# main_controller.net
KiCad netlist of a schematic drawn in EAGLE
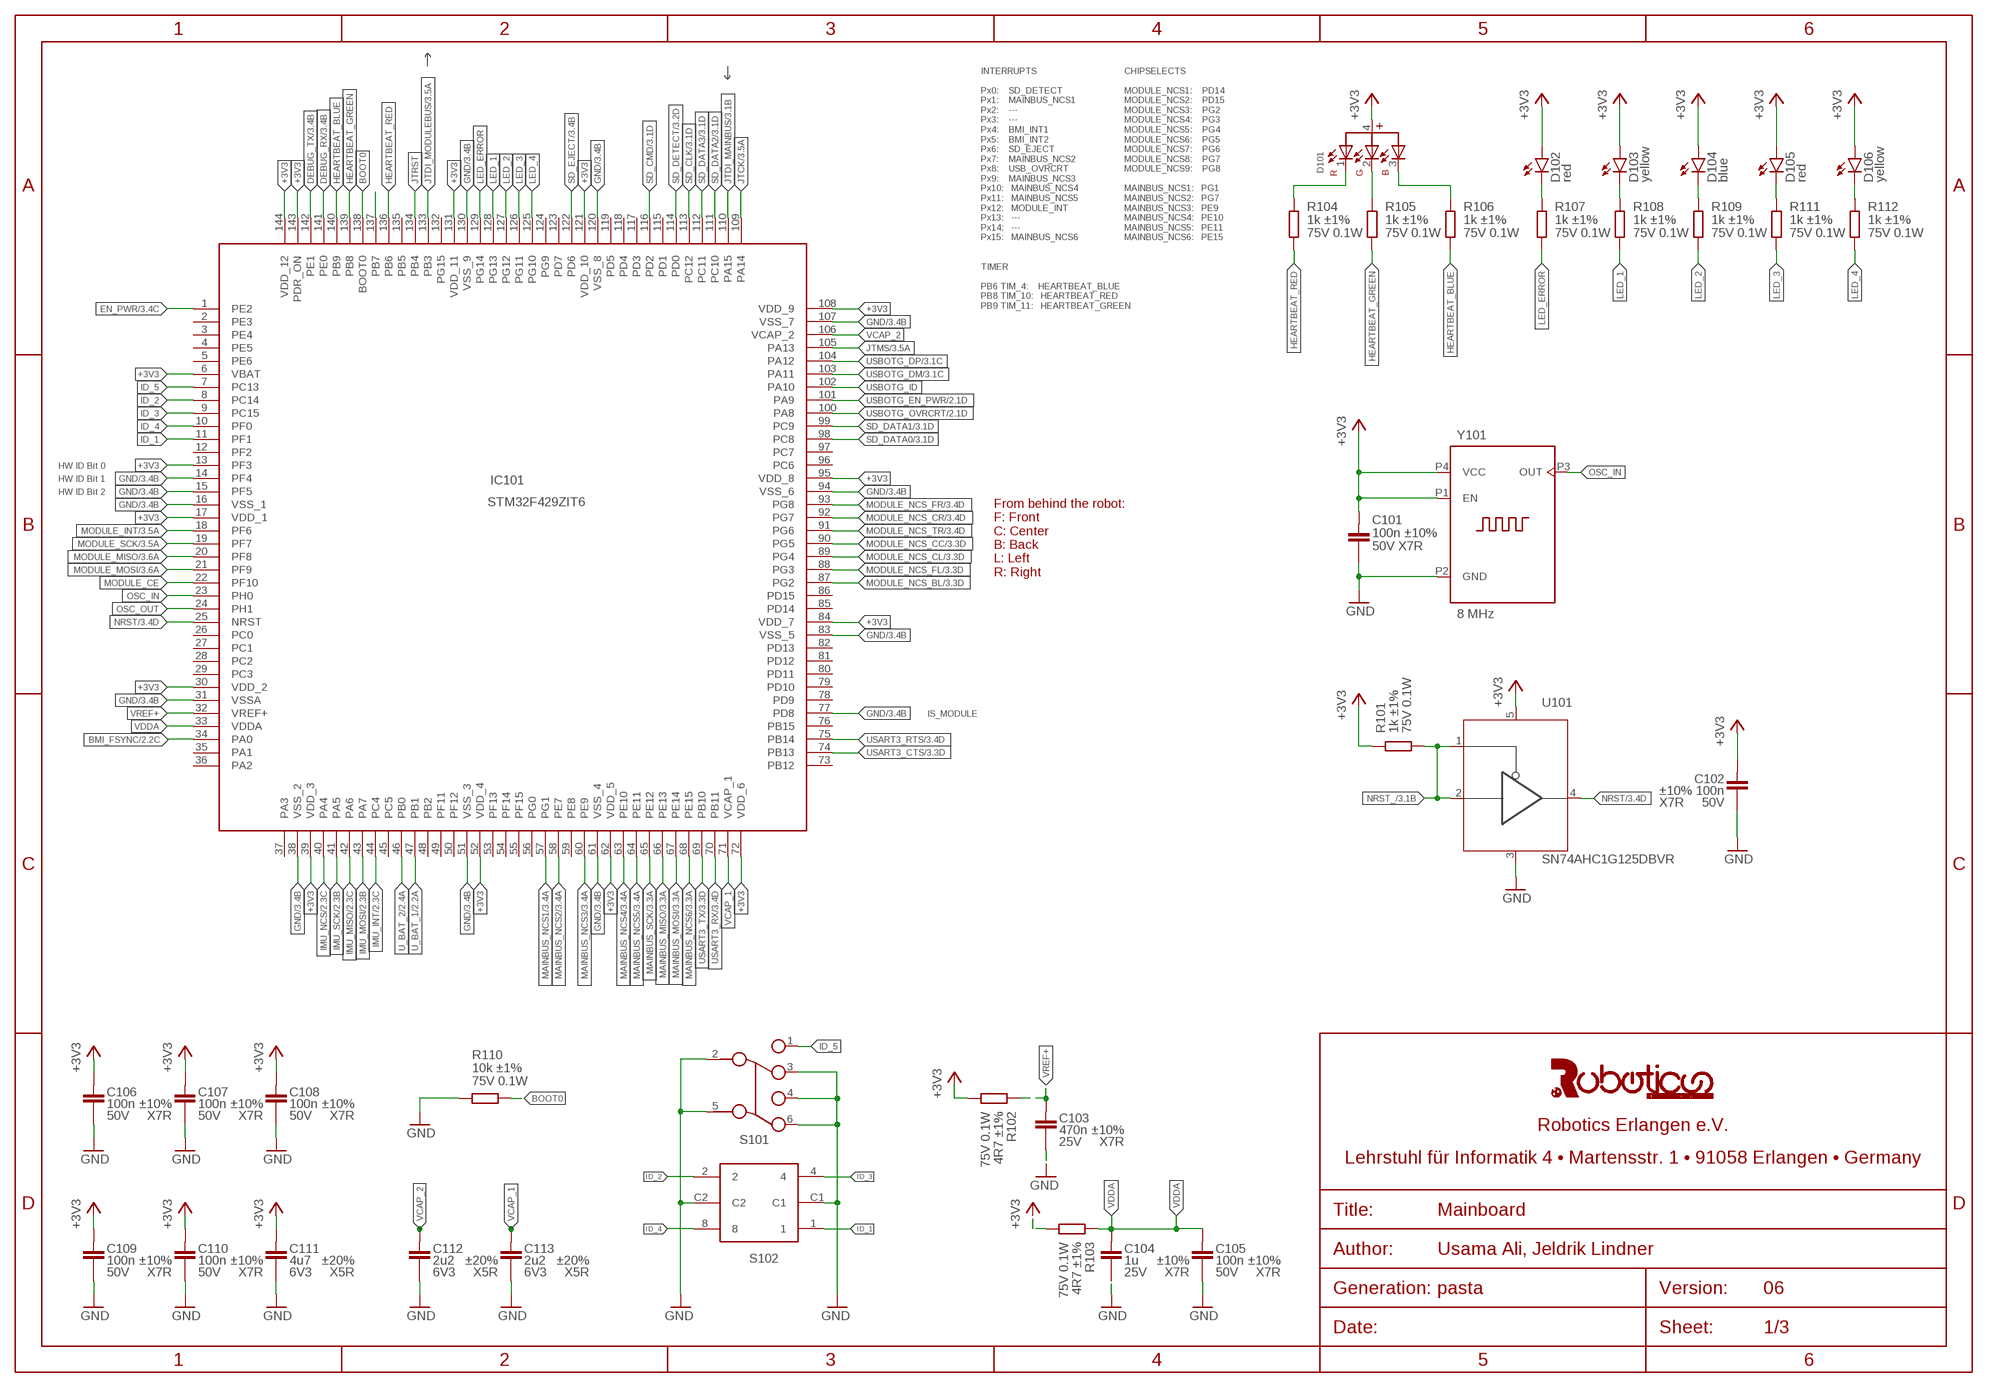
[diagram p0: schematic, sheet 1]
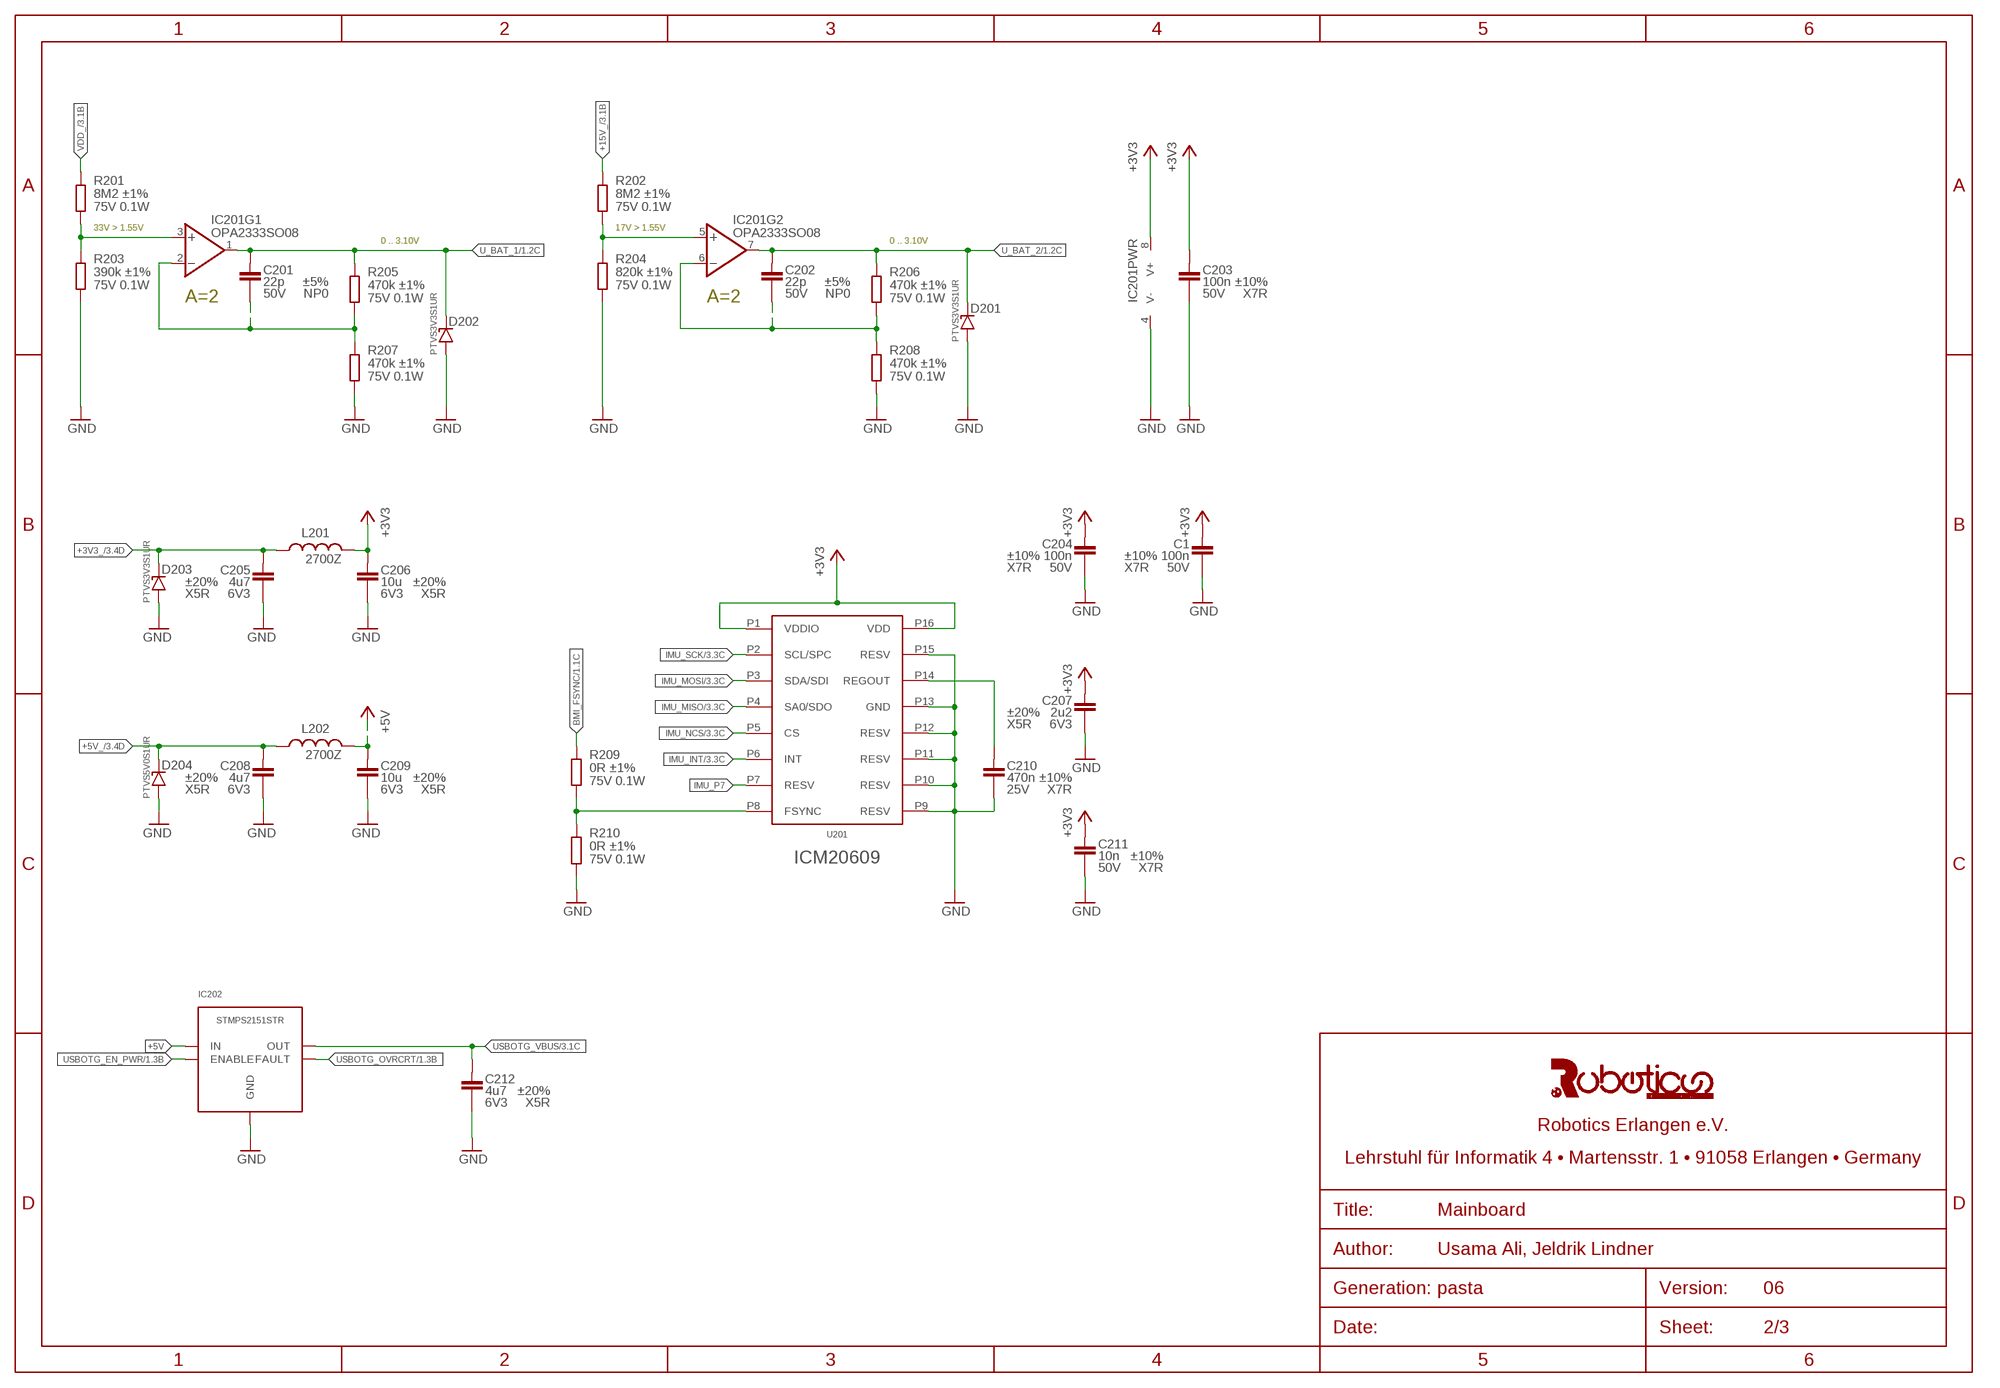
[diagram p1: schematic, sheet 2]
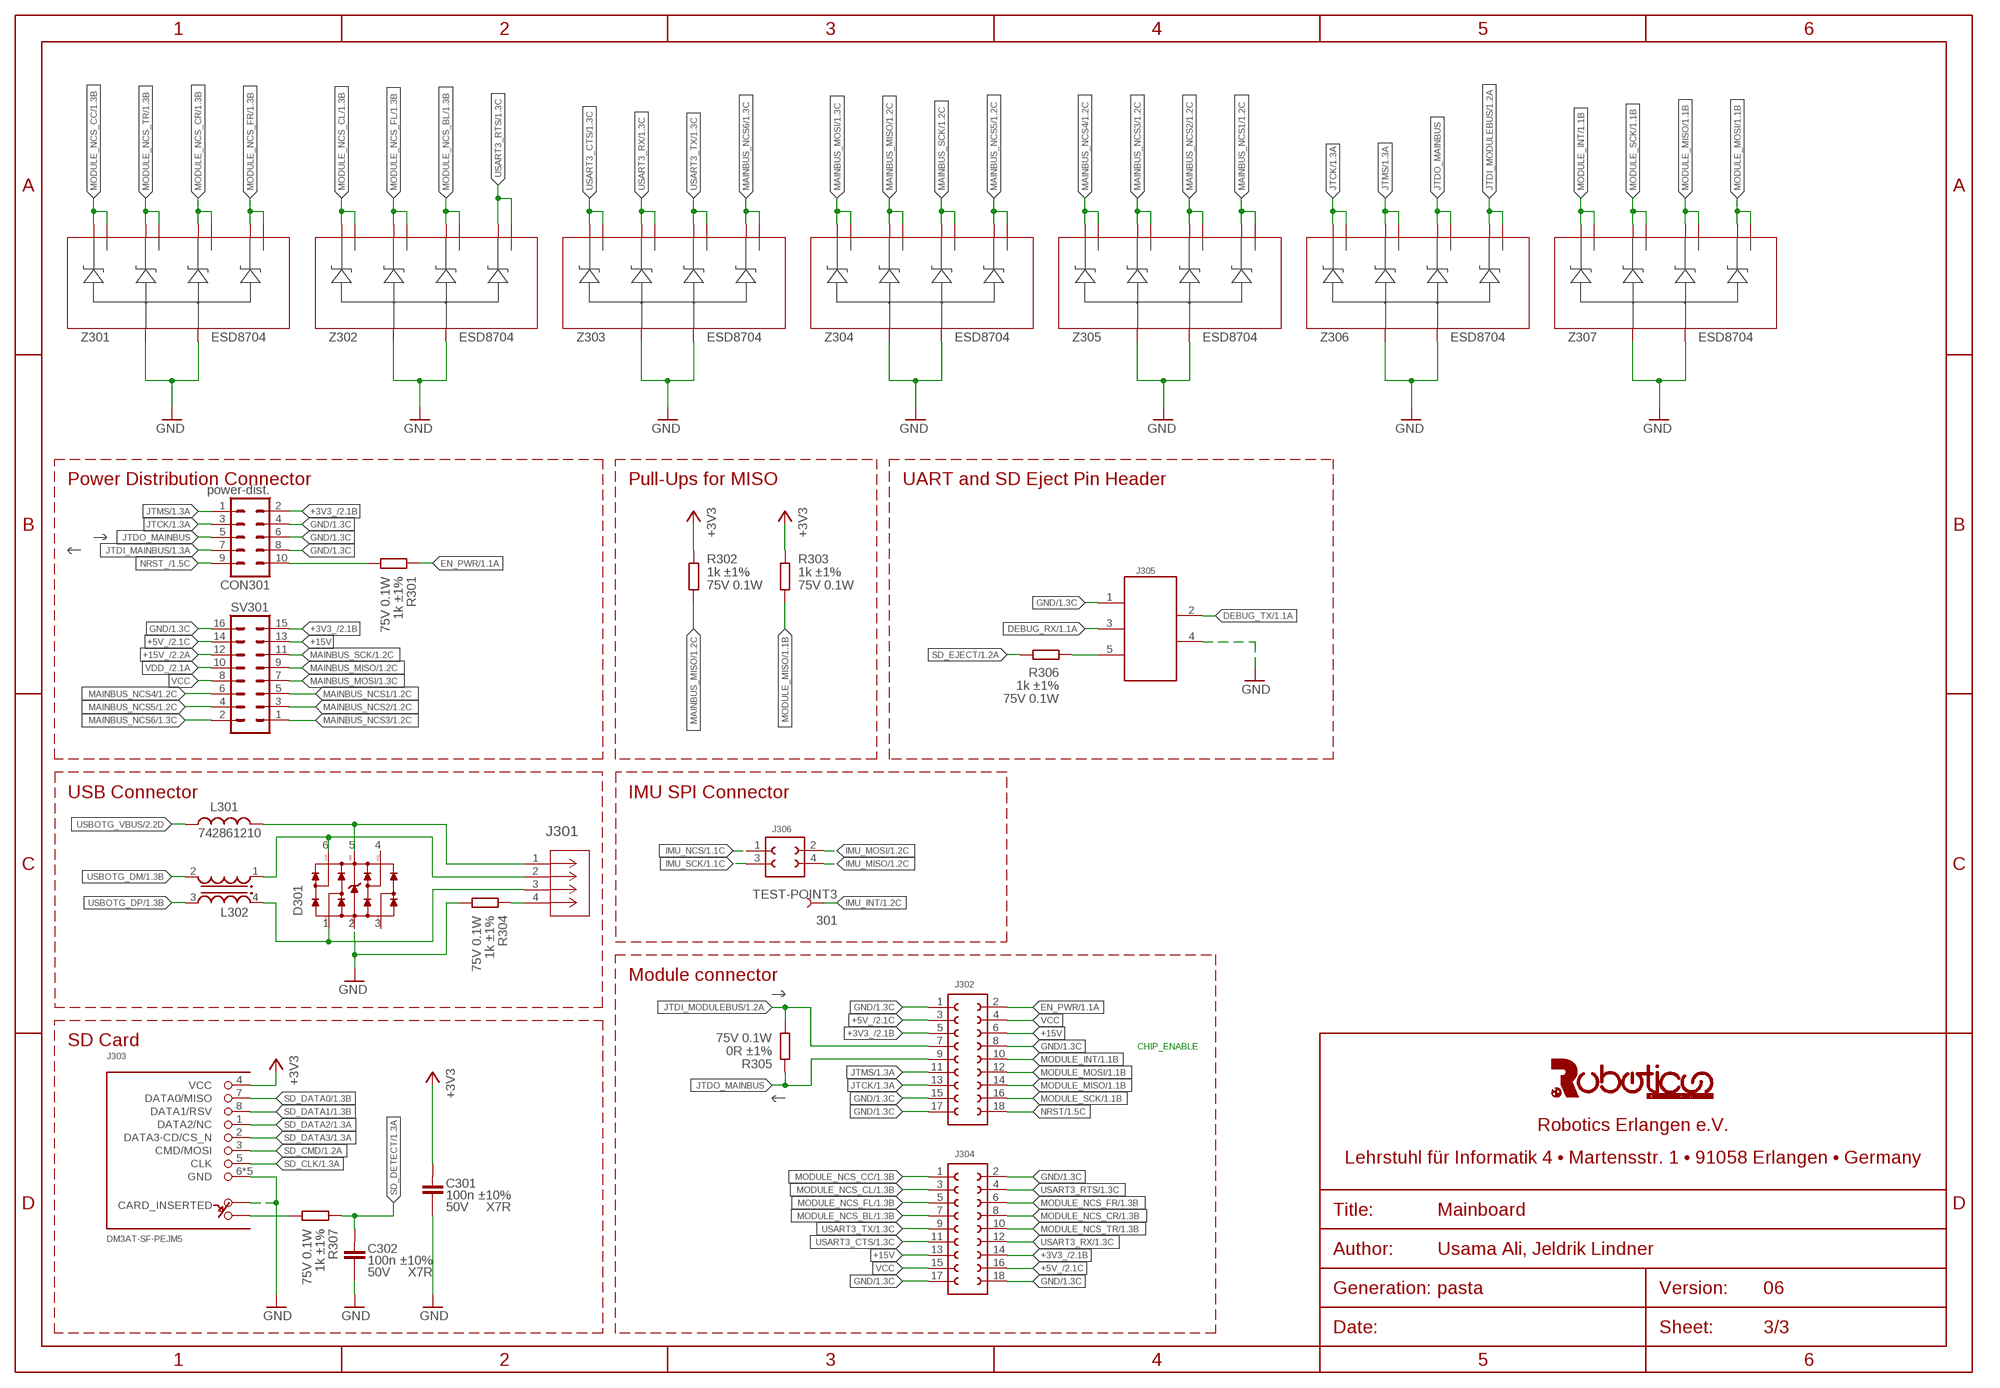
[diagram p2: schematic, sheet 3]

(export (version "E")
  (design (tool "Eeschema 10.0.6"))
  (components
    (comp (ref "301")
      (value "TEST-POINT3")
      (footprint "eagle-import:PAD.03X.03")
      (libsource (lib "eagle-import") (part "TEST-POINT3"))
    )
    (comp (ref "C301")
      (value "100n ±10% 50V X7R")
      (footprint "eagle-import:C0603")
      (fields
        (field (name "CAPACITANCE") "100n")
        (field (name "DIELECTRIC") "X7R")
        (field (name "MF") "Würth Elektronik")
        (field (name "MPN") "885012206095")
        (field (name "TOLERANCE") "±10%")
        (field (name "VOLTAGE") "50V")
      )
      (libsource (lib "eagle-import") (part "C(?)0603100NF,50V,"))
    )
    (comp (ref "C302")
      (value "100n ±10% 50V X7R")
      (footprint "eagle-import:C0603")
      (fields
        (field (name "CAPACITANCE") "100n")
        (field (name "DIELECTRIC") "X7R")
        (field (name "MF") "Würth Elektronik")
        (field (name "MPN") "885012206095")
        (field (name "TOLERANCE") "±10%")
        (field (name "VOLTAGE") "50V")
      )
      (libsource (lib "eagle-import") (part "C(?)0603100NF,50V,"))
    )
    (comp (ref "CON301")
      (value "power-dist.")
      (footprint "eagle-import:MA05-2")
      (fields
        (field (name "MF") "Würth Elektronik")
        (field (name "MPN") "61301021121")
        (field (name "MF_1") "Würth Elektronik")
        (field (name "MPN_1") "61301021121")
      )
      (libsource (lib "eagle-import") (part "MA05-2MA05-2"))
    )
    (comp (ref "D301")
      (value "WE-TVS_824001")
      (footprint "eagle-import:WE-TVS_SOT23-6L")
      (fields (field (name "MF") "Würth Elektronik") (field (name "MPN") "824001"))
      (libsource (lib "eagle-import") (part "WE-TVS_824001"))
    )
    (comp (ref "J301")
      (value "530480410")
      (footprint "eagle-import:CON_530480410_MOL")
      (fields
        (field (name "MF") "Molex Connector Corporation")
        (field (name "COPYRIGHT") "Copyright (C) 2022 Ultra Librarian. All rights reserved.")
      )
      (libsource (lib "eagle-import") (part "530480410"))
    )
    (comp (ref "J302")
      (value "610018243021")
      (footprint "eagle-import:610X1821821")
      (fields (field (name "MF") "Würth Elektronik"))
      (libsource (lib "eagle-import") (part "610018243021"))
    )
    (comp (ref "J303")
      (value "DM3AT-SF-PEJM5")
      (footprint "eagle-import:DM3AT-SF-PEJM5")
      (fields (field (name "MF") "Hirose Electric Co Ltd") (field (name "MPN") "DM3AT-SF-PEJM5"))
      (libsource (lib "eagle-import") (part "DM3AT-SF-PEJM5"))
    )
    (comp (ref "J304")
      (value "610018243021")
      (footprint "eagle-import:610X1821821")
      (fields (field (name "MF") "Würth Elektronik"))
      (libsource (lib "eagle-import") (part "610018243021"))
    )
    (comp (ref "J305")
      (value "61000618221")
      (footprint "eagle-import:61000618221")
      (fields (field (name "MF") "Würth Elektronik"))
      (libsource (lib "eagle-import") (part "61000618221"))
    )
    (comp (ref "J306")
      (value "623X0421021")
      (footprint "eagle-import:623X0421021")
      (libsource (lib "eagle-import") (part "623X0421021"))
    )
    (comp (ref "L301")
      (value "742861210")
      (footprint "eagle-import:WE-CBF_0603(W=2.6)")
      (fields (field (name "MF") "Würth Elektronik"))
      (libsource (lib "eagle-import") (part "742861210"))
    )
    (comp (ref "L302")
      (value "WE-CNSW_1206_744232090")
      (footprint "eagle-import:WE-CNSW_1206")
      (fields (field (name "MF") "Würth Elektronik") (field (name "MPN") "744232090"))
      (libsource (lib "eagle-import") (part "WE-CNSW_1206_744232090"))
    )
    (comp (ref "R301")
      (value "1k ±1% 75V 0.1W")
      (footprint "eagle-import:R0603")
      (fields
        (field (name "LINE1") "1k ±1%")
        (field (name "LINE2") "75V 0.1W")
        (field (name "MF") "YAGEO")
        (field (name "MPN") "RC0603FR-071KL")
        (field (name "POWER") "0.1W")
      )
      (libsource (lib "eagle-import") (part "R(?)06031.0K,75V,0.1W,"))
    )
    (comp (ref "R302")
      (value "1k ±1% 75V 0.1W")
      (footprint "eagle-import:R0603")
      (fields
        (field (name "LINE1") "1k ±1%")
        (field (name "LINE2") "75V 0.1W")
        (field (name "MF") "YAGEO")
        (field (name "MPN") "RC0603FR-071KL")
        (field (name "POWER") "0.1W")
      )
      (libsource (lib "eagle-import") (part "R(?)06031.0K,75V,0.1W,"))
    )
    (comp (ref "R303")
      (value "1k ±1% 75V 0.1W")
      (footprint "eagle-import:R0603")
      (fields
        (field (name "LINE1") "1k ±1%")
        (field (name "LINE2") "75V 0.1W")
        (field (name "MF") "YAGEO")
        (field (name "MPN") "RC0603FR-071KL")
        (field (name "POWER") "0.1W")
      )
      (libsource (lib "eagle-import") (part "R(?)06031.0K,75V,0.1W,"))
    )
    (comp (ref "R304")
      (value "1k ±1% 75V 0.1W")
      (footprint "eagle-import:R0603")
      (fields
        (field (name "LINE1") "1k ±1%")
        (field (name "LINE2") "75V 0.1W")
        (field (name "MF") "YAGEO")
        (field (name "MPN") "RC0603FR-071KL")
        (field (name "POWER") "0.1W")
      )
      (libsource (lib "eagle-import") (part "R(?)06031.0K,75V,0.1W,"))
    )
    (comp (ref "R305")
      (value "0R ±1% 75V 0.1W")
      (footprint "eagle-import:R0603")
      (fields
        (field (name "LINE1") "0R ±1%")
        (field (name "LINE2") "75V 0.1W")
        (field (name "MF") "YAGEO")
        (field (name "MPN") "RC0603FR-070RL")
        (field (name "POWER") "0.1W")
      )
      (libsource (lib "eagle-import") (part "R(?)06030R,75V,0.1W,"))
    )
    (comp (ref "R306")
      (value "1k ±1% 75V 0.1W")
      (footprint "eagle-import:R0603")
      (fields
        (field (name "LINE1") "1k ±1%")
        (field (name "LINE2") "75V 0.1W")
        (field (name "MF") "YAGEO")
        (field (name "MPN") "RC0603FR-071KL")
        (field (name "POWER") "0.1W")
      )
      (libsource (lib "eagle-import") (part "R(?)06031.0K,75V,0.1W,"))
    )
    (comp (ref "R307")
      (value "1k ±1% 75V 0.1W")
      (footprint "eagle-import:R0603")
      (fields
        (field (name "LINE1") "1k ±1%")
        (field (name "LINE2") "75V 0.1W")
        (field (name "MF") "YAGEO")
        (field (name "MPN") "RC0603FR-071KL")
        (field (name "POWER") "0.1W")
      )
      (libsource (lib "eagle-import") (part "R(?)06031.0K,75V,0.1W,"))
    )
    (comp (ref "SV301")
      (value "MA08-2")
      (footprint "eagle-import:MA08-2")
      (fields (field (name "MF") "Würth Elektronik") (field (name "MPN") "61301621121"))
      (libsource (lib "eagle-import") (part "MA08-2"))
    )
    (comp (ref "Z301")
      (value "ESD8704")
      (footprint "eagle-import:UDFN10")
      (fields (field (name "MF") "ON Semiconductor") (field (name "MPN") "ESD8704MUTAG"))
      (libsource (lib "eagle-import") (part "ESD8704"))
    )
    (comp (ref "Z302")
      (value "ESD8704")
      (footprint "eagle-import:UDFN10")
      (fields (field (name "MF") "ON Semiconductor") (field (name "MPN") "ESD8704MUTAG"))
      (libsource (lib "eagle-import") (part "ESD8704"))
    )
    (comp (ref "Z303")
      (value "ESD8704")
      (footprint "eagle-import:UDFN10")
      (fields (field (name "MF") "ON Semiconductor") (field (name "MPN") "ESD8704MUTAG"))
      (libsource (lib "eagle-import") (part "ESD8704"))
    )
    (comp (ref "Z304")
      (value "ESD8704")
      (footprint "eagle-import:UDFN10")
      (fields (field (name "MF") "ON Semiconductor") (field (name "MPN") "ESD8704MUTAG"))
      (libsource (lib "eagle-import") (part "ESD8704"))
    )
    (comp (ref "Z305")
      (value "ESD8704")
      (footprint "eagle-import:UDFN10")
      (fields (field (name "MF") "ON Semiconductor") (field (name "MPN") "ESD8704MUTAG"))
      (libsource (lib "eagle-import") (part "ESD8704"))
    )
    (comp (ref "Z306")
      (value "ESD8704")
      (footprint "eagle-import:UDFN10")
      (fields (field (name "MF") "ON Semiconductor") (field (name "MPN") "ESD8704MUTAG"))
      (libsource (lib "eagle-import") (part "ESD8704"))
    )
    (comp (ref "Z307")
      (value "ESD8704")
      (footprint "eagle-import:UDFN10")
      (fields (field (name "MF") "ON Semiconductor") (field (name "MPN") "ESD8704MUTAG"))
      (libsource (lib "eagle-import") (part "ESD8704"))
    )
    (comp (ref "C101")
      (value "100n ±10% 50V X7R")
      (footprint "eagle-import:C0603")
      (fields
        (field (name "LINE1") "100n ±10%")
        (field (name "LINE2") "50V X7R")
        (field (name "MF") "Würth Elektronik")
        (field (name "MPN") "885012206095")
        (field (name "TOLERANCE") "±10%")
      )
      (libsource (lib "eagle-import") (part "C(?)0603100NF,50V,"))
    )
    (comp (ref "C102")
      (value "100n ±10% 50V X7R")
      (footprint "eagle-import:C0603")
      (fields
        (field (name "CAPACITANCE") "100n")
        (field (name "DIELECTRIC") "X7R")
        (field (name "MF") "Würth Elektronik")
        (field (name "MPN") "885012206095")
        (field (name "TOLERANCE") "±10%")
        (field (name "VOLTAGE") "50V")
      )
      (libsource (lib "eagle-import") (part "C(?)0603100NF,50V,"))
    )
    (comp (ref "C103")
      (value "470n ±10% 25V X7R")
      (footprint "eagle-import:C0603")
      (fields
        (field (name "CAPACITANCE") "470n")
        (field (name "DIELECTRIC") "X7R")
        (field (name "MF") "Würth Elektronik")
        (field (name "MPN") "885012206075")
        (field (name "TOLERANCE") "±10%")
        (field (name "VOLTAGE") "25V")
      )
      (libsource (lib "eagle-import") (part "C(?)0603470NF,25V,"))
    )
    (comp (ref "C104")
      (value "1u ±10% 25V X7R")
      (footprint "eagle-import:C0603")
      (fields
        (field (name "CAPACITANCE") "1u")
        (field (name "DIELECTRIC") "X7R")
        (field (name "MF") "Würth Elektronik")
        (field (name "MPN") "885012206076")
        (field (name "TOLERANCE") "±10%")
        (field (name "VOLTAGE") "25V")
      )
      (libsource (lib "eagle-import") (part "C(?)06031.0UF,25V,"))
    )
    (comp (ref "C105")
      (value "100n ±10% 50V X7R")
      (footprint "eagle-import:C0603")
      (fields
        (field (name "CAPACITANCE") "100n")
        (field (name "DIELECTRIC") "X7R")
        (field (name "MF") "Würth Elektronik")
        (field (name "MPN") "885012206095")
        (field (name "TOLERANCE") "±10%")
        (field (name "VOLTAGE") "50V")
      )
      (libsource (lib "eagle-import") (part "C(?)0603100NF,50V,"))
    )
    (comp (ref "C106")
      (value "100n ±10% 50V X7R")
      (footprint "eagle-import:C0603")
      (fields
        (field (name "CAPACITANCE") "100n")
        (field (name "DIELECTRIC") "X7R")
        (field (name "MF") "Würth Elektronik")
        (field (name "MPN") "885012206095")
        (field (name "TOLERANCE") "±10%")
        (field (name "VOLTAGE") "50V")
      )
      (libsource (lib "eagle-import") (part "C(?)0603100NF,50V,"))
    )
    (comp (ref "C107")
      (value "100n ±10% 50V X7R")
      (footprint "eagle-import:C0603")
      (fields
        (field (name "CAPACITANCE") "100n")
        (field (name "DIELECTRIC") "X7R")
        (field (name "MF") "Würth Elektronik")
        (field (name "MPN") "885012206095")
        (field (name "TOLERANCE") "±10%")
        (field (name "VOLTAGE") "50V")
      )
      (libsource (lib "eagle-import") (part "C(?)0603100NF,50V,"))
    )
    (comp (ref "C108")
      (value "100n ±10% 50V X7R")
      (footprint "eagle-import:C0603")
      (fields
        (field (name "CAPACITANCE") "100n")
        (field (name "DIELECTRIC") "X7R")
        (field (name "MF") "Würth Elektronik")
        (field (name "MPN") "885012206095")
        (field (name "TOLERANCE") "±10%")
        (field (name "VOLTAGE") "50V")
      )
      (libsource (lib "eagle-import") (part "C(?)0603100NF,50V,"))
    )
    (comp (ref "C109")
      (value "100n ±10% 50V X7R")
      (footprint "eagle-import:C0603")
      (fields
        (field (name "CAPACITANCE") "100n")
        (field (name "DIELECTRIC") "X7R")
        (field (name "MF") "Würth Elektronik")
        (field (name "MPN") "885012206095")
        (field (name "TOLERANCE") "±10%")
        (field (name "VOLTAGE") "50V")
      )
      (libsource (lib "eagle-import") (part "C(?)0603100NF,50V,"))
    )
    (comp (ref "C110")
      (value "100n ±10% 50V X7R")
      (footprint "eagle-import:C0603")
      (fields
        (field (name "CAPACITANCE") "100n")
        (field (name "DIELECTRIC") "X7R")
        (field (name "MF") "Würth Elektronik")
        (field (name "MPN") "885012206095")
        (field (name "TOLERANCE") "±10%")
        (field (name "VOLTAGE") "50V")
      )
      (libsource (lib "eagle-import") (part "C(?)0603100NF,50V,"))
    )
    (comp (ref "C111")
      (value "4u7 ±20% 6V3 X5R")
      (footprint "eagle-import:C0603")
      (fields
        (field (name "CAPACITANCE") "4u7")
        (field (name "DIELECTRIC") "X5R")
        (field (name "MF") "Würth Elektronik")
        (field (name "MPN") "885012106005")
        (field (name "TOLERANCE") "±20%")
        (field (name "VOLTAGE") "6V3")
      )
      (libsource (lib "eagle-import") (part "C(?)06034.7UF,6.3V,"))
    )
    (comp (ref "C112")
      (value "2u2 ±20% 6V3 X5R")
      (footprint "eagle-import:C0603")
      (fields
        (field (name "CAPACITANCE") "2u2")
        (field (name "DIELECTRIC") "X5R")
        (field (name "MF") "Würth Elektronik")
        (field (name "MPN") "885012106004")
        (field (name "TOLERANCE") "±20%")
        (field (name "VOLTAGE") "6V3")
      )
      (libsource (lib "eagle-import") (part "C(?)06032.2UF,6.3V,"))
    )
    (comp (ref "C113")
      (value "2u2 ±20% 6V3 X5R")
      (footprint "eagle-import:C0603")
      (fields
        (field (name "CAPACITANCE") "2u2")
        (field (name "DIELECTRIC") "X5R")
        (field (name "MF") "Würth Elektronik")
        (field (name "MPN") "885012106004")
        (field (name "TOLERANCE") "±20%")
        (field (name "VOLTAGE") "6V3")
      )
      (libsource (lib "eagle-import") (part "C(?)06032.2UF,6.3V,"))
    )
    (comp (ref "D101")
      (value "WL-SFCD_0606_150066M153000")
      (footprint "eagle-import:WL-SFCX_0606")
      (fields (field (name "MF") "Würth Elektronik") (field (name "MPN") "150066M153000"))
      (libsource (lib "eagle-import") (part "WL-SFCD_0606_150066M153000"))
    )
    (comp (ref "D102")
      (value "red")
      (footprint "eagle-import:CHIPLED_0805")
      (fields (field (name "MF") "Würth Elektronik") (field (name "MPN") "150080RS75000"))
      (libsource (lib "eagle-import") (part "LEDCHIPLED_0805-RED-"))
    )
    (comp (ref "D103")
      (value "yellow")
      (footprint "eagle-import:CHIPLED_0805")
      (fields (field (name "MF") "Würth Elektronik") (field (name "MPN") "150080YS75000"))
      (libsource (lib "eagle-import") (part "LEDCHIPLED_0805-YELLOW-"))
    )
    (comp (ref "D104")
      (value "blue")
      (footprint "eagle-import:CHIPLED_0805")
      (fields (field (name "MF") "Würth Elektronik") (field (name "MPN") "150080BS75000"))
      (libsource (lib "eagle-import") (part "LEDCHIPLED_0805-BLUE-"))
    )
    (comp (ref "D105")
      (value "red")
      (footprint "eagle-import:CHIPLED_0805")
      (fields (field (name "MF") "Würth Elektronik") (field (name "MPN") "150080RS75000"))
      (libsource (lib "eagle-import") (part "LEDCHIPLED_0805-RED-"))
    )
    (comp (ref "D106")
      (value "yellow")
      (footprint "eagle-import:CHIPLED_0805")
      (fields (field (name "MF") "Würth Elektronik") (field (name "MPN") "150080YS75000"))
      (libsource (lib "eagle-import") (part "LEDCHIPLED_0805-YELLOW-"))
    )
    (comp (ref "IC101")
      (value "STM32F429ZIT6")
      (footprint "eagle-import:QFP50P2200X2200X160-144N")
      (fields (field (name "MF") "STMicroelectronics"))
      (libsource (lib "eagle-import") (part "STM32F429ZIT6"))
    )
    (comp (ref "R101")
      (value "1k ±1% 75V 0.1W")
      (footprint "eagle-import:R0603")
      (fields
        (field (name "LINE1") "1k ±1%")
        (field (name "LINE2") "75V 0.1W")
        (field (name "MF") "YAGEO")
        (field (name "MPN") "RC0603FR-071KL")
        (field (name "POWER") "0.1W")
      )
      (libsource (lib "eagle-import") (part "R(?)06031.0K,75V,0.1W,"))
    )
    (comp (ref "R102")
      (value "4R7 ±1% 75V 0.1W")
      (footprint "eagle-import:R0603")
      (fields
        (field (name "LINE1") "4R7 ±1%")
        (field (name "LINE2") "75V 0.1W")
        (field (name "MF") "YAGEO")
        (field (name "MPN") "RC0603FR-074R7L")
        (field (name "POWER") "0.1W")
      )
      (libsource (lib "eagle-import") (part "R(?)06034.7R,75V,0.1W,"))
    )
    (comp (ref "R103")
      (value "4R7 ±1% 75V 0.1W")
      (footprint "eagle-import:R0603")
      (fields
        (field (name "LINE1") "4R7 ±1%")
        (field (name "LINE2") "75V 0.1W")
        (field (name "MF") "YAGEO")
        (field (name "MPN") "RC0603FR-074R7L")
        (field (name "POWER") "0.1W")
      )
      (libsource (lib "eagle-import") (part "R(?)06034.7R,75V,0.1W,"))
    )
    (comp (ref "R104")
      (value "1k ±1% 75V 0.1W")
      (footprint "eagle-import:R0603")
      (fields
        (field (name "LINE1") "1k ±1%")
        (field (name "LINE2") "75V 0.1W")
        (field (name "MF") "YAGEO")
        (field (name "MPN") "RC0603FR-071KL")
        (field (name "POWER") "0.1W")
      )
      (libsource (lib "eagle-import") (part "R(?)06031.0K,75V,0.1W,"))
    )
    (comp (ref "R105")
      (value "1k ±1% 75V 0.1W")
      (footprint "eagle-import:R0603")
      (fields
        (field (name "LINE1") "1k ±1%")
        (field (name "LINE2") "75V 0.1W")
        (field (name "MF") "YAGEO")
        (field (name "MPN") "RC0603FR-071KL")
        (field (name "POWER") "0.1W")
      )
      (libsource (lib "eagle-import") (part "R(?)06031.0K,75V,0.1W,"))
    )
    (comp (ref "R106")
      (value "1k ±1% 75V 0.1W")
      (footprint "eagle-import:R0603")
      (fields
        (field (name "LINE1") "1k ±1%")
        (field (name "LINE2") "75V 0.1W")
        (field (name "MF") "YAGEO")
        (field (name "MPN") "RC0603FR-071KL")
        (field (name "POWER") "0.1W")
      )
      (libsource (lib "eagle-import") (part "R(?)06031.0K,75V,0.1W,"))
    )
    (comp (ref "R107")
      (value "1k ±1% 75V 0.1W")
      (footprint "eagle-import:R0603")
      (fields
        (field (name "LINE1") "1k ±1%")
        (field (name "LINE2") "75V 0.1W")
        (field (name "MF") "YAGEO")
        (field (name "MPN") "RC0603FR-071KL")
        (field (name "POWER") "0.1W")
      )
      (libsource (lib "eagle-import") (part "R(?)06031.0K,75V,0.1W,"))
    )
    (comp (ref "R108")
      (value "1k ±1% 75V 0.1W")
      (footprint "eagle-import:R0603")
      (fields
        (field (name "LINE1") "1k ±1%")
        (field (name "LINE2") "75V 0.1W")
        (field (name "MF") "YAGEO")
        (field (name "MPN") "RC0603FR-071KL")
        (field (name "POWER") "0.1W")
      )
      (libsource (lib "eagle-import") (part "R(?)06031.0K,75V,0.1W,"))
    )
    (comp (ref "R109")
      (value "1k ±1% 75V 0.1W")
      (footprint "eagle-import:R0603")
      (fields
        (field (name "LINE1") "1k ±1%")
        (field (name "LINE2") "75V 0.1W")
        (field (name "MF") "YAGEO")
        (field (name "MPN") "RC0603FR-071KL")
        (field (name "POWER") "0.1W")
      )
      (libsource (lib "eagle-import") (part "R(?)06031.0K,75V,0.1W,"))
    )
    (comp (ref "R110")
      (value "10k ±1% 75V 0.1W")
      (footprint "eagle-import:R0603")
      (fields
        (field (name "LINE1") "10k ±1%")
        (field (name "LINE2") "75V 0.1W")
        (field (name "MF") "YAGEO")
        (field (name "MPN") "RC0603FR-0710KL")
        (field (name "POWER") "0.1W")
      )
      (libsource (lib "eagle-import") (part "R(?)060310K,75V,0.1W,"))
    )
    (comp (ref "R111")
      (value "1k ±1% 75V 0.1W")
      (footprint "eagle-import:R0603")
      (fields
        (field (name "LINE1") "1k ±1%")
        (field (name "LINE2") "75V 0.1W")
        (field (name "MF") "YAGEO")
        (field (name "MPN") "RC0603FR-071KL")
        (field (name "POWER") "0.1W")
      )
      (libsource (lib "eagle-import") (part "R(?)06031.0K,75V,0.1W,"))
    )
    (comp (ref "R112")
      (value "1k ±1% 75V 0.1W")
      (footprint "eagle-import:R0603")
      (fields
        (field (name "LINE1") "1k ±1%")
        (field (name "LINE2") "75V 0.1W")
        (field (name "MF") "YAGEO")
        (field (name "MPN") "RC0603FR-071KL")
        (field (name "POWER") "0.1W")
      )
      (libsource (lib "eagle-import") (part "R(?)06031.0K,75V,0.1W,"))
    )
    (comp (ref "S101")
      (value "452403012014")
      (footprint "eagle-import:452403012014")
      (fields (field (name "MF") "Würth Elektronik"))
      (libsource (lib "eagle-import") (part "452403012014"))
    )
    (comp (ref "S102")
      (value "428542320816")
      (footprint "eagle-import:428542320816")
      (fields (field (name "MF") "Würth Elektronik"))
      (libsource (lib "eagle-import") (part "428542320816"))
    )
    (comp (ref "U101")
      (value "SN74AHC1G125DBVR")
      (footprint "eagle-import:SOT23-5")
      (fields (field (name "MF") "Texas Instruments"))
      (libsource (lib "eagle-import") (part "SN74AHC1G125DBVR"))
    )
    (comp (ref "Y101")
      (value "8 MHz")
      (footprint "eagle-import:830207192009")
      (fields (field (name "MF") "Würth Elektronik") (field (name "MPN") "830207192009"))
      (libsource (lib "eagle-import") (part "830200971920"))
    )
    (comp (ref "C1")
      (value "100n ±10% 50V X7R")
      (footprint "eagle-import:C0603")
      (fields
        (field (name "CAPACITANCE") "100n")
        (field (name "DIELECTRIC") "X7R")
        (field (name "MF") "Würth Elektronik")
        (field (name "MPN") "885012206095")
        (field (name "TOLERANCE") "±10%")
        (field (name "VOLTAGE") "50V")
      )
      (libsource (lib "eagle-import") (part "C(?)0603100NF,50V,"))
    )
    (comp (ref "C201")
      (value "22p ±5% 50V NP0")
      (footprint "eagle-import:C0603")
      (fields
        (field (name "CAPACITANCE") "22p")
        (field (name "DIELECTRIC") "NP0")
        (field (name "MF") "Würth Elektronik")
        (field (name "MPN") "885012006053")
        (field (name "TOLERANCE") "±5%")
        (field (name "VOLTAGE") "50V")
      )
      (libsource (lib "eagle-import") (part "C(?)060322PF,50V,"))
    )
    (comp (ref "C202")
      (value "22p ±5% 50V NP0")
      (footprint "eagle-import:C0603")
      (fields
        (field (name "CAPACITANCE") "22p")
        (field (name "DIELECTRIC") "NP0")
        (field (name "MF") "Würth Elektronik")
        (field (name "MPN") "885012006053")
        (field (name "TOLERANCE") "±5%")
        (field (name "VOLTAGE") "50V")
      )
      (libsource (lib "eagle-import") (part "C(?)060322PF,50V,"))
    )
    (comp (ref "C203")
      (value "100n ±10% 50V X7R")
      (footprint "eagle-import:C0603")
      (fields
        (field (name "CAPACITANCE") "100n")
        (field (name "DIELECTRIC") "X7R")
        (field (name "MF") "Würth Elektronik")
        (field (name "MPN") "885012206095")
        (field (name "TOLERANCE") "±10%")
        (field (name "VOLTAGE") "50V")
      )
      (libsource (lib "eagle-import") (part "C(?)0603100NF,50V,"))
    )
    (comp (ref "C204")
      (value "100n ±10% 50V X7R")
      (footprint "eagle-import:C0603")
      (fields
        (field (name "CAPACITANCE") "100n")
        (field (name "DIELECTRIC") "X7R")
        (field (name "MF") "Würth Elektronik")
        (field (name "MPN") "885012206095")
        (field (name "TOLERANCE") "±10%")
        (field (name "VOLTAGE") "50V")
      )
      (libsource (lib "eagle-import") (part "C(?)0603100NF,50V,"))
    )
    (comp (ref "C205")
      (value "4u7 ±20% 6V3 X5R")
      (footprint "eagle-import:C0603")
      (fields
        (field (name "CAPACITANCE") "4u7")
        (field (name "DIELECTRIC") "X5R")
        (field (name "MF") "Würth Elektronik")
        (field (name "MPN") "885012106005")
        (field (name "TOLERANCE") "±20%")
        (field (name "VOLTAGE") "6V3")
      )
      (libsource (lib "eagle-import") (part "C(?)06034.7UF,6.3V,"))
    )
    (comp (ref "C206")
      (value "10u ±20% 6V3 X5R")
      (footprint "eagle-import:C0603")
      (fields
        (field (name "CAPACITANCE") "10u")
        (field (name "DIELECTRIC") "X5R")
        (field (name "MF") "Würth Elektronik")
        (field (name "MPN") "885012106006")
        (field (name "TOLERANCE") "±20%")
        (field (name "VOLTAGE") "6V3")
      )
      (libsource (lib "eagle-import") (part "C(?)060310UF,6.3V,"))
    )
    (comp (ref "C207")
      (value "2u2 ±20% 6V3 X5R")
      (footprint "eagle-import:C0603")
      (fields
        (field (name "CAPACITANCE") "2u2")
        (field (name "DIELECTRIC") "X5R")
        (field (name "MF") "Würth Elektronik")
        (field (name "MPN") "885012106004")
        (field (name "TOLERANCE") "±20%")
        (field (name "VOLTAGE") "6V3")
      )
      (libsource (lib "eagle-import") (part "C(?)06032.2UF,6.3V,"))
    )
    (comp (ref "C208")
      (value "4u7 ±20% 6V3 X5R")
      (footprint "eagle-import:C0603")
      (fields
        (field (name "CAPACITANCE") "4u7")
        (field (name "DIELECTRIC") "X5R")
        (field (name "MF") "Würth Elektronik")
        (field (name "MPN") "885012106005")
        (field (name "TOLERANCE") "±20%")
        (field (name "VOLTAGE") "6V3")
      )
      (libsource (lib "eagle-import") (part "C(?)06034.7UF,6.3V,"))
    )
    (comp (ref "C209")
      (value "10u ±20% 6V3 X5R")
      (footprint "eagle-import:C0603")
      (fields
        (field (name "CAPACITANCE") "10u")
        (field (name "DIELECTRIC") "X5R")
        (field (name "MF") "Würth Elektronik")
        (field (name "MPN") "885012106006")
        (field (name "TOLERANCE") "±20%")
        (field (name "VOLTAGE") "6V3")
      )
      (libsource (lib "eagle-import") (part "C(?)060310UF,6.3V,"))
    )
    (comp (ref "C210")
      (value "470n ±10% 25V X7R")
      (footprint "eagle-import:C0603")
      (fields
        (field (name "CAPACITANCE") "470n")
        (field (name "DIELECTRIC") "X7R")
        (field (name "MF") "Würth Elektronik")
        (field (name "MPN") "885012206075")
        (field (name "TOLERANCE") "±10%")
        (field (name "VOLTAGE") "25V")
      )
      (libsource (lib "eagle-import") (part "C(?)0603470NF,25V,"))
    )
    (comp (ref "C211")
      (value "10n ±10% 50V X7R")
      (footprint "eagle-import:C0603")
      (fields
        (field (name "CAPACITANCE") "10n")
        (field (name "DIELECTRIC") "X7R")
        (field (name "MF") "Würth Elektronik")
        (field (name "MPN") "885012206089")
        (field (name "TOLERANCE") "±10%")
        (field (name "VOLTAGE") "50V")
      )
      (libsource (lib "eagle-import") (part "C(?)060310NF,50V,"))
    )
    (comp (ref "C212")
      (value "4u7 ±20% 6V3 X5R")
      (footprint "eagle-import:C0603")
      (fields
        (field (name "CAPACITANCE") "4u7")
        (field (name "DIELECTRIC") "X5R")
        (field (name "MF") "Würth Elektronik")
        (field (name "MPN") "885012106005")
        (field (name "TOLERANCE") "±20%")
        (field (name "VOLTAGE") "6V3")
      )
      (libsource (lib "eagle-import") (part "C(?)06034.7UF,6.3V,"))
    )
    (comp (ref "D201")
      (value "PTVS3V3S1UR")
      (footprint "eagle-import:SOD123")
      (fields
        (field (name "MF") "Nexperia")
        (field (name "MPN") " PTVS3V3S1UR,115")
        (field (name "MF_1") "Nexperia")
      )
      (libsource (lib "eagle-import") (part "PTVSS1UR3V3"))
    )
    (comp (ref "D202")
      (value "PTVS3V3S1UR")
      (footprint "eagle-import:SOD123")
      (fields
        (field (name "MF") "Nexperia")
        (field (name "MPN") " PTVS3V3S1UR,115")
        (field (name "MF_1") "Nexperia")
      )
      (libsource (lib "eagle-import") (part "PTVSS1UR3V3"))
    )
    (comp (ref "D203")
      (value "PTVS3V3S1UR")
      (footprint "eagle-import:SOD123")
      (fields
        (field (name "MF") "Nexperia")
        (field (name "MPN") " PTVS3V3S1UR,115")
        (field (name "MF_1") "Nexperia")
      )
      (libsource (lib "eagle-import") (part "PTVSS1UR3V3"))
    )
    (comp (ref "D204")
      (value "PTVS5V0S1UR")
      (footprint "eagle-import:SOD123")
      (fields
        (field (name "MF") "Nexperia")
        (field (name "MPN") " PTVS5V0S1UR,115")
        (field (name "MF_1") "Nexperia")
      )
      (libsource (lib "eagle-import") (part "PTVSS1UR5V0"))
    )
    (comp (ref "IC201")
      (value "OPA2333SO08")
      (footprint "eagle-import:SO08")
      (fields
        (field (name "MF") "Texas Instruments")
        (field (name "MPN") "OPA2333AIDR")
        (field (name "MF_1") "Texas Instruments")
        (field (name "MOUSER") "595-OPA2333AIDR")
        (field (name "MPN_1") "OPA2333AIDR")
      )
      (libsource (lib "eagle-import") (part "OPA2333SO08"))
    )
    (comp (ref "IC202")
      (value "STMPS2151STR")
      (footprint "eagle-import:SOT23-5_1")
      (fields (field (name "MF") "STMicroelectronics"))
      (libsource (lib "eagle-import") (part "STMPS2151STR"))
    )
    (comp (ref "L201")
      (value "2700Z")
      (footprint "eagle-import:WE-CBF_0603(W=2.6)")
      (fields
        (field (name "MF") "Würth Elektronik")
        (field (name "MPN") "742861160")
        (field (name "MF_1") "Würth Elektronik")
      )
      (libsource (lib "eagle-import") (part "742861160"))
    )
    (comp (ref "L202")
      (value "2700Z")
      (footprint "eagle-import:WE-CBF_0603(W=2.6)")
      (fields
        (field (name "MF") "Würth Elektronik")
        (field (name "MPN") "742861210")
        (field (name "MF_1") "Würth Elektronik")
      )
      (libsource (lib "eagle-import") (part "742861210"))
    )
    (comp (ref "R201")
      (value "8M2 ±1% 75V 0.1W")
      (footprint "eagle-import:R0603")
      (fields
        (field (name "LINE1") "8M2 ±1%")
        (field (name "LINE2") "75V 0.1W")
        (field (name "MF") "YAGEO")
        (field (name "MPN") "RC0603FR-078M2L")
        (field (name "POWER") "0.1W")
      )
      (libsource (lib "eagle-import") (part "R(?)06038.2M,75V,0.1W,"))
    )
    (comp (ref "R202")
      (value "8M2 ±1% 75V 0.1W")
      (footprint "eagle-import:R0603")
      (fields
        (field (name "LINE1") "8M2 ±1%")
        (field (name "LINE2") "75V 0.1W")
        (field (name "MF") "YAGEO")
        (field (name "MPN") "RC0603FR-078M2L")
        (field (name "POWER") "0.1W")
      )
      (libsource (lib "eagle-import") (part "R(?)06038.2M,75V,0.1W,"))
    )
    (comp (ref "R203")
      (value "390k ±1% 75V 0.1W")
      (footprint "eagle-import:R0603")
      (fields
        (field (name "LINE1") "390k ±1%")
        (field (name "LINE2") "75V 0.1W")
        (field (name "MF") "YAGEO")
        (field (name "MPN") "RC0603FR-07390KL")
        (field (name "POWER") "0.1W")
      )
      (libsource (lib "eagle-import") (part "R(?)0603390K,75V,0.1W,"))
    )
    (comp (ref "R204")
      (value "820k ±1% 75V 0.1W")
      (footprint "eagle-import:R0603")
      (fields
        (field (name "LINE1") "820k ±1%")
        (field (name "LINE2") "75V 0.1W")
        (field (name "MF") "YAGEO")
        (field (name "MPN") "RC0603FR-07820KL")
        (field (name "POWER") "0.1W")
      )
      (libsource (lib "eagle-import") (part "R(?)0603820K,75V,0.1W,"))
    )
    (comp (ref "R205")
      (value "470k ±1% 75V 0.1W")
      (footprint "eagle-import:R0603")
      (fields
        (field (name "LINE1") "470k ±1%")
        (field (name "LINE2") "75V 0.1W")
        (field (name "MF") "YAGEO")
        (field (name "MPN") "RC0603FR-07470KL")
        (field (name "POWER") "0.1W")
      )
      (libsource (lib "eagle-import") (part "R(?)0603470K,75V,0.1W,"))
    )
    (comp (ref "R206")
      (value "470k ±1% 75V 0.1W")
      (footprint "eagle-import:R0603")
      (fields
        (field (name "LINE1") "470k ±1%")
        (field (name "LINE2") "75V 0.1W")
        (field (name "MF") "YAGEO")
        (field (name "MPN") "RC0603FR-07470KL")
        (field (name "POWER") "0.1W")
      )
      (libsource (lib "eagle-import") (part "R(?)0603470K,75V,0.1W,"))
    )
    (comp (ref "R207")
      (value "470k ±1% 75V 0.1W")
      (footprint "eagle-import:R0603")
      (fields
        (field (name "LINE1") "470k ±1%")
        (field (name "LINE2") "75V 0.1W")
        (field (name "MF") "YAGEO")
        (field (name "MPN") "RC0603FR-07470KL")
        (field (name "POWER") "0.1W")
      )
      (libsource (lib "eagle-import") (part "R(?)0603470K,75V,0.1W,"))
    )
    (comp (ref "R208")
      (value "470k ±1% 75V 0.1W")
      (footprint "eagle-import:R0603")
      (fields
        (field (name "LINE1") "470k ±1%")
        (field (name "LINE2") "75V 0.1W")
        (field (name "MF") "YAGEO")
        (field (name "MPN") "RC0603FR-07470KL")
        (field (name "POWER") "0.1W")
      )
      (libsource (lib "eagle-import") (part "R(?)0603470K,75V,0.1W,"))
    )
    (comp (ref "R209")
      (value "0R ±1% 75V 0.1W")
      (footprint "eagle-import:R0603")
      (fields
        (field (name "LINE1") "0R ±1%")
        (field (name "LINE2") "75V 0.1W")
        (field (name "MF") "YAGEO")
        (field (name "MPN") "RC0603FR-070RL")
        (field (name "POWER") "0.1W")
      )
      (libsource (lib "eagle-import") (part "R(?)06030R,75V,0.1W,"))
    )
    (comp (ref "R210")
      (value "0R ±1% 75V 0.1W")
      (footprint "eagle-import:R0603")
      (fields
        (field (name "LINE1") "0R ±1%")
        (field (name "LINE2") "75V 0.1W")
        (field (name "MF") "YAGEO")
        (field (name "MPN") "RC0603FR-070RL")
        (field (name "POWER") "0.1W")
      )
      (libsource (lib "eagle-import") (part "R(?)06030R,75V,0.1W,"))
    )
    (comp (ref "U201")
      (value "ICM20609")
      (footprint "eagle-import:ICM20609")
      (fields (field (name "MF") "TDK InvenSense"))
      (libsource (lib "eagle-import") (part "ICM20609"))
    )
  )
  (nets
    (net (code "1") (name "+3V3") (class "Default")
      (node (ref "C1") (pin "1") (pinfunction "1_1") (pintype "passive"))
      (node (ref "C101") (pin "1") (pinfunction "1_1") (pintype "passive"))
      (node (ref "C102") (pin "1") (pinfunction "1_1") (pintype "passive"))
      (node (ref "C106") (pin "1") (pinfunction "1_1") (pintype "passive"))
      (node (ref "C107") (pin "1") (pinfunction "1_1") (pintype "passive"))
      (node (ref "C108") (pin "1") (pinfunction "1_1") (pintype "passive"))
      (node (ref "C109") (pin "1") (pinfunction "1_1") (pintype "passive"))
      (node (ref "C110") (pin "1") (pinfunction "1_1") (pintype "passive"))
      (node (ref "C111") (pin "1") (pinfunction "1_1") (pintype "passive"))
      (node (ref "C203") (pin "1") (pinfunction "1_1") (pintype "passive"))
      (node (ref "C204") (pin "1") (pinfunction "1_1") (pintype "passive"))
      (node (ref "C206") (pin "1") (pinfunction "1_1") (pintype "passive"))
      (node (ref "C207") (pin "1") (pinfunction "1_1") (pintype "passive"))
      (node (ref "C211") (pin "1") (pinfunction "1_1") (pintype "passive"))
      (node (ref "C301") (pin "1") (pinfunction "1_1") (pintype "passive"))
      (node (ref "D101") (pin "4") (pinfunction "4_4") (pintype "passive"))
      (node (ref "D102") (pin "A") (pinfunction "A_A") (pintype "passive"))
      (node (ref "D103") (pin "A") (pinfunction "A_A") (pintype "passive"))
      (node (ref "D104") (pin "A") (pinfunction "A_A") (pintype "passive"))
      (node (ref "D105") (pin "A") (pinfunction "A_A") (pintype "passive"))
      (node (ref "D106") (pin "A") (pinfunction "A_A") (pintype "passive"))
      (node (ref "IC101") (pin "108") (pinfunction "VDD_9_108") (pintype "power_in"))
      (node (ref "IC101") (pin "121") (pinfunction "VDD_10_121") (pintype "power_in"))
      (node (ref "IC101") (pin "13") (pinfunction "PF3_13") (pintype "bidirectional"))
      (node (ref "IC101") (pin "131") (pinfunction "VDD_11_131") (pintype "power_in"))
      (node (ref "IC101") (pin "143") (pinfunction "PDR_ON_143") (pintype "bidirectional"))
      (node (ref "IC101") (pin "144") (pinfunction "VDD_12_144") (pintype "power_in"))
      (node (ref "IC101") (pin "17") (pinfunction "VDD_1_17") (pintype "power_in"))
      (node (ref "IC101") (pin "30") (pinfunction "VDD_2_30") (pintype "power_in"))
      (node (ref "IC101") (pin "39") (pinfunction "VDD_3_39") (pintype "power_in"))
      (node (ref "IC101") (pin "52") (pinfunction "VDD_4_52") (pintype "power_in"))
      (node (ref "IC101") (pin "6") (pinfunction "VBAT_6") (pintype "bidirectional"))
      (node (ref "IC101") (pin "62") (pinfunction "VDD_5_62") (pintype "power_in"))
      (node (ref "IC101") (pin "72") (pinfunction "VDD_6_72") (pintype "power_in"))
      (node (ref "IC101") (pin "84") (pinfunction "VDD_7_84") (pintype "power_in"))
      (node (ref "IC101") (pin "95") (pinfunction "VDD_8_95") (pintype "power_in"))
      (node (ref "IC201") (pin "8") (pinfunction "V+_8") (pintype "power_in"))
      (node (ref "J303") (pin "4") (pinfunction "VCC_4") (pintype "bidirectional"))
      (node (ref "L201") (pin "1") (pinfunction "1_1") (pintype "passive"))
      (node (ref "R101") (pin "2") (pinfunction "2_2") (pintype "passive"))
      (node (ref "R102") (pin "1") (pinfunction "1_1") (pintype "passive"))
      (node (ref "R103") (pin "1") (pinfunction "1_1") (pintype "passive"))
      (node (ref "R302") (pin "2") (pinfunction "2_2") (pintype "passive"))
      (node (ref "R303") (pin "2") (pinfunction "2_2") (pintype "passive"))
      (node (ref "U101") (pin "5") (pinfunction "VCC_5") (pintype "power_in"))
      (node (ref "U201") (pin "P1") (pinfunction "VDDIO_P1") (pintype "bidirectional"))
      (node (ref "U201") (pin "P16") (pinfunction "VDD_P16") (pintype "bidirectional"))
      (node (ref "Y101") (pin "P1") (pinfunction "EN_P1") (pintype "input"))
      (node (ref "Y101") (pin "P4") (pinfunction "VCC_P4") (pintype "power_in"))
    )
    (net (code "2") (name "+3V3_") (class "Default")
      (node (ref "C205") (pin "1") (pinfunction "1_1") (pintype "passive"))
      (node (ref "CON301") (pin "2") (pinfunction "2_2") (pintype "passive"))
      (node (ref "D203") (pin "C") (pinfunction "KATHODE_C") (pintype "bidirectional"))
      (node (ref "J302") (pin "5") (pinfunction "3_5") (pintype "passive"))
      (node (ref "J304") (pin "14") (pinfunction "12_14") (pintype "passive"))
      (node (ref "L201") (pin "2") (pinfunction "2_2") (pintype "passive"))
      (node (ref "SV301") (pin "15") (pinfunction "15_15") (pintype "passive"))
    )
    (net (code "3") (name "+5V") (class "Default")
      (node (ref "C209") (pin "1") (pinfunction "1_1") (pintype "passive"))
      (node (ref "IC202") (pin "5") (pinfunction "IN_5") (pintype "power_in"))
      (node (ref "L202") (pin "1") (pinfunction "1_1") (pintype "passive"))
    )
    (net (code "4") (name "+5V_") (class "Default")
      (node (ref "C208") (pin "1") (pinfunction "1_1") (pintype "passive"))
      (node (ref "D204") (pin "C") (pinfunction "KATHODE_C") (pintype "bidirectional"))
      (node (ref "J302") (pin "3") (pinfunction "2_3") (pintype "passive"))
      (node (ref "J304") (pin "16") (pinfunction "11_16") (pintype "passive"))
      (node (ref "L202") (pin "2") (pinfunction "2_2") (pintype "passive"))
      (node (ref "SV301") (pin "14") (pinfunction "14_14") (pintype "passive"))
    )
    (net (code "5") (name "+15V") (class "Default")
      (node (ref "J302") (pin "6") (pinfunction "16_6") (pintype "passive"))
      (node (ref "J304") (pin "13") (pinfunction "7_13") (pintype "passive"))
      (node (ref "SV301") (pin "13") (pinfunction "13_13") (pintype "passive"))
    )
    (net (code "6") (name "+15V_") (class "Default")
      (node (ref "R202") (pin "2") (pinfunction "2_2") (pintype "passive"))
      (node (ref "SV301") (pin "12") (pinfunction "12_12") (pintype "passive"))
    )
    (net (code "7") (name "BMI_FSYNC") (class "Default")
      (node (ref "IC101") (pin "34") (pinfunction "PA0_34") (pintype "bidirectional"))
      (node (ref "R209") (pin "2") (pinfunction "2_2") (pintype "passive"))
    )
    (net (code "8") (name "BOOT0") (class "Default")
      (node (ref "IC101") (pin "138") (pinfunction "BOOT0_138") (pintype "bidirectional"))
      (node (ref "R110") (pin "1") (pinfunction "1_1") (pintype "passive"))
    )
    (net (code "9") (name "DEBUG_RX") (class "Default")
      (node (ref "IC101") (pin "141") (pinfunction "PE0_141") (pintype "bidirectional"))
      (node (ref "J305") (pin "3") (pinfunction "3_3") (pintype "passive"))
    )
    (net (code "10") (name "DEBUG_TX") (class "Default")
      (node (ref "IC101") (pin "142") (pinfunction "PE1_142") (pintype "bidirectional"))
      (node (ref "J305") (pin "2") (pinfunction "2_2") (pintype "passive"))
    )
    (net (code "11") (name "EN_PWR") (class "Default")
      (node (ref "IC101") (pin "1") (pinfunction "PE2_1") (pintype "bidirectional"))
      (node (ref "J302") (pin "2") (pinfunction "18_2") (pintype "passive"))
      (node (ref "R301") (pin "2") (pinfunction "2_2") (pintype "passive"))
    )
    (net (code "12") (name "GND") (class "Default")
      (node (ref "C1") (pin "2") (pinfunction "2_2") (pintype "passive"))
      (node (ref "C101") (pin "2") (pinfunction "2_2") (pintype "passive"))
      (node (ref "C102") (pin "2") (pinfunction "2_2") (pintype "passive"))
      (node (ref "C103") (pin "2") (pinfunction "2_2") (pintype "passive"))
      (node (ref "C104") (pin "2") (pinfunction "2_2") (pintype "passive"))
      (node (ref "C105") (pin "2") (pinfunction "2_2") (pintype "passive"))
      (node (ref "C106") (pin "2") (pinfunction "2_2") (pintype "passive"))
      (node (ref "C107") (pin "2") (pinfunction "2_2") (pintype "passive"))
      (node (ref "C108") (pin "2") (pinfunction "2_2") (pintype "passive"))
      (node (ref "C109") (pin "2") (pinfunction "2_2") (pintype "passive"))
      (node (ref "C110") (pin "2") (pinfunction "2_2") (pintype "passive"))
      (node (ref "C111") (pin "2") (pinfunction "2_2") (pintype "passive"))
      (node (ref "C112") (pin "2") (pinfunction "2_2") (pintype "passive"))
      (node (ref "C113") (pin "2") (pinfunction "2_2") (pintype "passive"))
      (node (ref "C203") (pin "2") (pinfunction "2_2") (pintype "passive"))
      (node (ref "C204") (pin "2") (pinfunction "2_2") (pintype "passive"))
      (node (ref "C205") (pin "2") (pinfunction "2_2") (pintype "passive"))
      (node (ref "C206") (pin "2") (pinfunction "2_2") (pintype "passive"))
      (node (ref "C207") (pin "2") (pinfunction "2_2") (pintype "passive"))
      (node (ref "C208") (pin "2") (pinfunction "2_2") (pintype "passive"))
      (node (ref "C209") (pin "2") (pinfunction "2_2") (pintype "passive"))
      (node (ref "C210") (pin "2") (pinfunction "2_2") (pintype "passive"))
      (node (ref "C211") (pin "2") (pinfunction "2_2") (pintype "passive"))
      (node (ref "C212") (pin "2") (pinfunction "2_2") (pintype "passive"))
      (node (ref "C301") (pin "2") (pinfunction "2_2") (pintype "passive"))
      (node (ref "C302") (pin "2") (pinfunction "2_2") (pintype "passive"))
      (node (ref "CON301") (pin "4") (pinfunction "4_4") (pintype "passive"))
      (node (ref "CON301") (pin "6") (pinfunction "6_6") (pintype "passive"))
      (node (ref "CON301") (pin "8") (pinfunction "8_8") (pintype "passive"))
      (node (ref "D201") (pin "A") (pinfunction "ANODE_A") (pintype "bidirectional"))
      (node (ref "D202") (pin "A") (pinfunction "ANODE_A") (pintype "bidirectional"))
      (node (ref "D203") (pin "A") (pinfunction "ANODE_A") (pintype "bidirectional"))
      (node (ref "D204") (pin "A") (pinfunction "ANODE_A") (pintype "bidirectional"))
      (node (ref "D301") (pin "2") (pinfunction "GND_2") (pintype "power_in"))
      (node (ref "IC101") (pin "107") (pinfunction "VSS_7_107") (pintype "power_in"))
      (node (ref "IC101") (pin "120") (pinfunction "VSS_8_120") (pintype "power_in"))
      (node (ref "IC101") (pin "130") (pinfunction "VSS_9_130") (pintype "power_in"))
      (node (ref "IC101") (pin "14") (pinfunction "PF4_14") (pintype "bidirectional"))
      (node (ref "IC101") (pin "15") (pinfunction "PF5_15") (pintype "bidirectional"))
      (node (ref "IC101") (pin "16") (pinfunction "VSS_1_16") (pintype "power_in"))
      (node (ref "IC101") (pin "31") (pinfunction "VSSA_31") (pintype "power_in"))
      (node (ref "IC101") (pin "38") (pinfunction "VSS_2_38") (pintype "power_in"))
      (node (ref "IC101") (pin "51") (pinfunction "VSS_3_51") (pintype "power_in"))
      (node (ref "IC101") (pin "61") (pinfunction "VSS_4_61") (pintype "power_in"))
      (node (ref "IC101") (pin "77") (pinfunction "PD8_77") (pintype "bidirectional"))
      (node (ref "IC101") (pin "83") (pinfunction "VSS_5_83") (pintype "power_in"))
      (node (ref "IC101") (pin "94") (pinfunction "VSS_6_94") (pintype "power_in"))
      (node (ref "IC201") (pin "4") (pinfunction "V-_4") (pintype "power_in"))
      (node (ref "IC202") (pin "2") (pinfunction "GND_2") (pintype "power_in"))
      (node (ref "J302") (pin "1") (pinfunction "1_1") (pintype "passive"))
      (node (ref "J302") (pin "15") (pinfunction "8_15") (pintype "passive"))
      (node (ref "J302") (pin "17") (pinfunction "9_17") (pintype "passive"))
      (node (ref "J302") (pin "8") (pinfunction "15_8") (pintype "passive"))
      (node (ref "J303") (pin "6") (pinfunction "GND_6") (pintype "bidirectional"))
      (node (ref "J303") (pin "A") (pinfunction "A_A") (pintype "bidirectional"))
      (node (ref "J303") (pin "MOUNT0") (pinfunction "GND_MOUNT0") (pintype "bidirectional"))
      (node (ref "J303") (pin "MOUNT1") (pinfunction "GND_MOUNT1") (pintype "bidirectional"))
      (node (ref "J303") (pin "MOUNT2") (pinfunction "GND_MOUNT2") (pintype "bidirectional"))
      (node (ref "J303") (pin "MOUNT3") (pinfunction "GND_MOUNT3") (pintype "bidirectional"))
      (node (ref "J304") (pin "17") (pinfunction "9_17") (pintype "passive"))
      (node (ref "J304") (pin "18") (pinfunction "10_18") (pintype "passive"))
      (node (ref "J304") (pin "2") (pinfunction "18_2") (pintype "passive"))
      (node (ref "J305") (pin "1") (pinfunction "1_1") (pintype "passive"))
      (node (ref "J305") (pin "4") (pinfunction "4_4") (pintype "passive"))
      (node (ref "R110") (pin "2") (pinfunction "2_2") (pintype "passive"))
      (node (ref "R203") (pin "1") (pinfunction "1_1") (pintype "passive"))
      (node (ref "R204") (pin "1") (pinfunction "1_1") (pintype "passive"))
      (node (ref "R207") (pin "1") (pinfunction "1_1") (pintype "passive"))
      (node (ref "R208") (pin "1") (pinfunction "1_1") (pintype "passive"))
      (node (ref "R210") (pin "1") (pinfunction "1_1") (pintype "passive"))
      (node (ref "R304") (pin "1") (pinfunction "1_1") (pintype "passive"))
      (node (ref "S101") (pin "2") (pinfunction "2_2") (pintype "passive"))
      (node (ref "S101") (pin "3") (pinfunction "3_3") (pintype "passive"))
      (node (ref "S101") (pin "4") (pinfunction "4_4") (pintype "passive"))
      (node (ref "S101") (pin "5") (pinfunction "5_5") (pintype "passive"))
      (node (ref "S101") (pin "6") (pinfunction "6_6") (pintype "passive"))
      (node (ref "S102") (pin "C1") (pinfunction "C1_C1") (pintype "passive"))
      (node (ref "S102") (pin "C2") (pinfunction "C2_C2") (pintype "passive"))
      (node (ref "SV301") (pin "16") (pinfunction "16_16") (pintype "passive"))
      (node (ref "U101") (pin "3") (pinfunction "GND_3") (pintype "power_in"))
      (node (ref "U201") (pin "P10") (pinfunction "RESV_P10") (pintype "bidirectional"))
      (node (ref "U201") (pin "P11") (pinfunction "RESV_P11") (pintype "bidirectional"))
      (node (ref "U201") (pin "P12") (pinfunction "RESV_P12") (pintype "bidirectional"))
      (node (ref "U201") (pin "P13") (pinfunction "GND_P13") (pintype "bidirectional"))
      (node (ref "U201") (pin "P15") (pinfunction "RESV_P15") (pintype "bidirectional"))
      (node (ref "U201") (pin "P9") (pinfunction "RESV_P9") (pintype "bidirectional"))
      (node (ref "Y101") (pin "P2") (pinfunction "GND_P2") (pintype "power_in"))
      (node (ref "Z301") (pin "3") (pinfunction "A_3") (pintype "passive"))
      (node (ref "Z301") (pin "8") (pinfunction "A_8") (pintype "passive"))
      (node (ref "Z302") (pin "3") (pinfunction "A_3") (pintype "passive"))
      (node (ref "Z302") (pin "8") (pinfunction "A_8") (pintype "passive"))
      (node (ref "Z303") (pin "3") (pinfunction "A_3") (pintype "passive"))
      (node (ref "Z303") (pin "8") (pinfunction "A_8") (pintype "passive"))
      (node (ref "Z304") (pin "3") (pinfunction "A_3") (pintype "passive"))
      (node (ref "Z304") (pin "8") (pinfunction "A_8") (pintype "passive"))
      (node (ref "Z305") (pin "3") (pinfunction "A_3") (pintype "passive"))
      (node (ref "Z305") (pin "8") (pinfunction "A_8") (pintype "passive"))
      (node (ref "Z306") (pin "3") (pinfunction "A_3") (pintype "passive"))
      (node (ref "Z306") (pin "8") (pinfunction "A_8") (pintype "passive"))
      (node (ref "Z307") (pin "3") (pinfunction "A_3") (pintype "passive"))
      (node (ref "Z307") (pin "8") (pinfunction "A_8") (pintype "passive"))
    )
    (net (code "13") (name "HEARTBEAT_BLUE") (class "Default")
      (node (ref "IC101") (pin "140") (pinfunction "PB9_140") (pintype "bidirectional"))
      (node (ref "R106") (pin "1") (pinfunction "1_1") (pintype "passive"))
    )
    (net (code "14") (name "HEARTBEAT_GREEN") (class "Default")
      (node (ref "IC101") (pin "139") (pinfunction "PB8_139") (pintype "bidirectional"))
      (node (ref "R105") (pin "1") (pinfunction "1_1") (pintype "passive"))
    )
    (net (code "15") (name "HEARTBEAT_RED") (class "Default")
      (node (ref "IC101") (pin "136") (pinfunction "PB6_136") (pintype "bidirectional"))
      (node (ref "R104") (pin "1") (pinfunction "1_1") (pintype "passive"))
    )
    (net (code "16") (name "ID_1") (class "Default")
      (node (ref "IC101") (pin "11") (pinfunction "PF1_11") (pintype "bidirectional"))
      (node (ref "S102") (pin "1") (pinfunction "1_1") (pintype "passive"))
    )
    (net (code "17") (name "ID_2") (class "Default")
      (node (ref "IC101") (pin "8") (pinfunction "PC14_8") (pintype "bidirectional"))
      (node (ref "S102") (pin "2") (pinfunction "2_2") (pintype "passive"))
    )
    (net (code "18") (name "ID_3") (class "Default")
      (node (ref "IC101") (pin "9") (pinfunction "PC15_9") (pintype "bidirectional"))
      (node (ref "S102") (pin "4") (pinfunction "4_4") (pintype "passive"))
    )
    (net (code "19") (name "ID_4") (class "Default")
      (node (ref "IC101") (pin "10") (pinfunction "PF0_10") (pintype "bidirectional"))
      (node (ref "S102") (pin "8") (pinfunction "8_8") (pintype "passive"))
    )
    (net (code "20") (name "ID_5") (class "Default")
      (node (ref "IC101") (pin "7") (pinfunction "PC13_7") (pintype "bidirectional"))
      (node (ref "S101") (pin "1") (pinfunction "1_1") (pintype "passive"))
    )
    (net (code "21") (name "IMU_INT") (class "Default")
      (node (ref "301") (pin "P$1") (pinfunction "1_P$1") (pintype "bidirectional"))
      (node (ref "IC101") (pin "44") (pinfunction "PC4_44") (pintype "bidirectional"))
      (node (ref "U201") (pin "P6") (pinfunction "INT_P6") (pintype "bidirectional"))
    )
    (net (code "22") (name "IMU_MISO") (class "Default")
      (node (ref "IC101") (pin "42") (pinfunction "PA6_42") (pintype "bidirectional"))
      (node (ref "J306") (pin "4") (pinfunction "3_4") (pintype "passive"))
      (node (ref "U201") (pin "P4") (pinfunction "SA0/SDO_P4") (pintype "bidirectional"))
    )
    (net (code "23") (name "IMU_MOSI") (class "Default")
      (node (ref "IC101") (pin "43") (pinfunction "PA7_43") (pintype "bidirectional"))
      (node (ref "J306") (pin "2") (pinfunction "4_2") (pintype "passive"))
      (node (ref "U201") (pin "P3") (pinfunction "SDA/SDI_P3") (pintype "bidirectional"))
    )
    (net (code "24") (name "IMU_NCS") (class "Default")
      (node (ref "IC101") (pin "40") (pinfunction "PA4_40") (pintype "bidirectional"))
      (node (ref "J306") (pin "1") (pinfunction "1_1") (pintype "passive"))
      (node (ref "U201") (pin "P5") (pinfunction "CS_P5") (pintype "bidirectional"))
    )
    (net (code "25") (name "IMU_P7") (class "Default")
      (node (ref "U201") (pin "P7") (pinfunction "RESV_P7") (pintype "bidirectional"))
    )
    (net (code "26") (name "IMU_SCK") (class "Default")
      (node (ref "IC101") (pin "41") (pinfunction "PA5_41") (pintype "bidirectional"))
      (node (ref "J306") (pin "3") (pinfunction "2_3") (pintype "passive"))
      (node (ref "U201") (pin "P2") (pinfunction "SCL/SPC_P2") (pintype "bidirectional"))
    )
    (net (code "27") (name "JTCK") (class "Default")
      (node (ref "CON301") (pin "3") (pinfunction "3_3") (pintype "passive"))
      (node (ref "IC101") (pin "109") (pinfunction "PA14_109") (pintype "bidirectional"))
      (node (ref "J302") (pin "13") (pinfunction "7_13") (pintype "passive"))
      (node (ref "Z306") (pin "1") (pinfunction "C1_1") (pintype "passive"))
      (node (ref "Z306") (pin "10") (pinfunction "D1_10") (pintype "passive"))
    )
    (net (code "28") (name "JTDI_MAINBUS") (class "Default")
      (node (ref "CON301") (pin "7") (pinfunction "7_7") (pintype "passive"))
      (node (ref "IC101") (pin "110") (pinfunction "PA15_110") (pintype "bidirectional"))
    )
    (net (code "29") (name "JTDI_MODULEBUS") (class "Default")
      (node (ref "IC101") (pin "133") (pinfunction "PB3_133") (pintype "bidirectional"))
      (node (ref "J302") (pin "7") (pinfunction "4_7") (pintype "passive"))
      (node (ref "R305") (pin "1") (pinfunction "1_1") (pintype "passive"))
      (node (ref "Z306") (pin "5") (pinfunction "C4_5") (pintype "passive"))
      (node (ref "Z306") (pin "6") (pinfunction "D4_6") (pintype "passive"))
    )
    (net (code "30") (name "JTDO_MAINBUS") (class "Default")
      (node (ref "CON301") (pin "5") (pinfunction "5_5") (pintype "passive"))
      (node (ref "J302") (pin "9") (pinfunction "5_9") (pintype "passive"))
      (node (ref "R305") (pin "2") (pinfunction "2_2") (pintype "passive"))
      (node (ref "Z306") (pin "4") (pinfunction "C3_4") (pintype "passive"))
      (node (ref "Z306") (pin "7") (pinfunction "D3_7") (pintype "passive"))
    )
    (net (code "31") (name "JTMS") (class "Default")
      (node (ref "CON301") (pin "1") (pinfunction "1_1") (pintype "passive"))
      (node (ref "IC101") (pin "105") (pinfunction "PA13_105") (pintype "bidirectional"))
      (node (ref "J302") (pin "11") (pinfunction "6_11") (pintype "passive"))
      (node (ref "Z306") (pin "2") (pinfunction "C2_2") (pintype "passive"))
      (node (ref "Z306") (pin "9") (pinfunction "D2_9") (pintype "passive"))
    )
    (net (code "32") (name "JTRST") (class "Default")
      (node (ref "IC101") (pin "134") (pinfunction "PB4_134") (pintype "bidirectional"))
    )
    (net (code "33") (name "LED_1") (class "Default")
      (node (ref "IC101") (pin "128") (pinfunction "PG13_128") (pintype "bidirectional"))
      (node (ref "R108") (pin "1") (pinfunction "1_1") (pintype "passive"))
    )
    (net (code "34") (name "LED_2") (class "Default")
      (node (ref "IC101") (pin "127") (pinfunction "PG12_127") (pintype "bidirectional"))
      (node (ref "R109") (pin "1") (pinfunction "1_1") (pintype "passive"))
    )
    (net (code "35") (name "LED_3") (class "Default")
      (node (ref "IC101") (pin "126") (pinfunction "PG11_126") (pintype "bidirectional"))
      (node (ref "R111") (pin "1") (pinfunction "1_1") (pintype "passive"))
    )
    (net (code "36") (name "LED_4") (class "Default")
      (node (ref "IC101") (pin "125") (pinfunction "PG10_125") (pintype "bidirectional"))
      (node (ref "R112") (pin "1") (pinfunction "1_1") (pintype "passive"))
    )
    (net (code "37") (name "LED_ERROR") (class "Default")
      (node (ref "IC101") (pin "129") (pinfunction "PG14_129") (pintype "bidirectional"))
      (node (ref "R107") (pin "1") (pinfunction "1_1") (pintype "passive"))
    )
    (net (code "38") (name "MAINBUS_MISO") (class "Default")
      (node (ref "IC101") (pin "66") (pinfunction "PE13_66") (pintype "bidirectional"))
      (node (ref "R302") (pin "1") (pinfunction "1_1") (pintype "passive"))
      (node (ref "SV301") (pin "9") (pinfunction "9_9") (pintype "passive"))
      (node (ref "Z304") (pin "2") (pinfunction "C2_2") (pintype "passive"))
      (node (ref "Z304") (pin "9") (pinfunction "D2_9") (pintype "passive"))
    )
    (net (code "39") (name "MAINBUS_MOSI") (class "Default")
      (node (ref "IC101") (pin "67") (pinfunction "PE14_67") (pintype "bidirectional"))
      (node (ref "SV301") (pin "7") (pinfunction "7_7") (pintype "passive"))
      (node (ref "Z304") (pin "1") (pinfunction "C1_1") (pintype "passive"))
      (node (ref "Z304") (pin "10") (pinfunction "D1_10") (pintype "passive"))
    )
    (net (code "40") (name "MAINBUS_NCS1") (class "Default")
      (node (ref "IC101") (pin "57") (pinfunction "PG1_57") (pintype "bidirectional"))
      (node (ref "SV301") (pin "5") (pinfunction "5_5") (pintype "passive"))
      (node (ref "Z305") (pin "5") (pinfunction "C4_5") (pintype "passive"))
      (node (ref "Z305") (pin "6") (pinfunction "D4_6") (pintype "passive"))
    )
    (net (code "41") (name "MAINBUS_NCS2") (class "Default")
      (node (ref "IC101") (pin "58") (pinfunction "PE7_58") (pintype "bidirectional"))
      (node (ref "SV301") (pin "3") (pinfunction "3_3") (pintype "passive"))
      (node (ref "Z305") (pin "4") (pinfunction "C3_4") (pintype "passive"))
      (node (ref "Z305") (pin "7") (pinfunction "D3_7") (pintype "passive"))
    )
    (net (code "42") (name "MAINBUS_NCS3") (class "Default")
      (node (ref "IC101") (pin "60") (pinfunction "PE9_60") (pintype "bidirectional"))
      (node (ref "SV301") (pin "1") (pinfunction "1_1") (pintype "passive"))
      (node (ref "Z305") (pin "2") (pinfunction "C2_2") (pintype "passive"))
      (node (ref "Z305") (pin "9") (pinfunction "D2_9") (pintype "passive"))
    )
    (net (code "43") (name "MAINBUS_NCS4") (class "Default")
      (node (ref "IC101") (pin "63") (pinfunction "PE10_63") (pintype "bidirectional"))
      (node (ref "SV301") (pin "6") (pinfunction "6_6") (pintype "passive"))
      (node (ref "Z305") (pin "1") (pinfunction "C1_1") (pintype "passive"))
      (node (ref "Z305") (pin "10") (pinfunction "D1_10") (pintype "passive"))
    )
    (net (code "44") (name "MAINBUS_NCS5") (class "Default")
      (node (ref "IC101") (pin "64") (pinfunction "PE11_64") (pintype "bidirectional"))
      (node (ref "SV301") (pin "4") (pinfunction "4_4") (pintype "passive"))
      (node (ref "Z304") (pin "5") (pinfunction "C4_5") (pintype "passive"))
      (node (ref "Z304") (pin "6") (pinfunction "D4_6") (pintype "passive"))
    )
    (net (code "45") (name "MAINBUS_NCS6") (class "Default")
      (node (ref "IC101") (pin "68") (pinfunction "PE15_68") (pintype "bidirectional"))
      (node (ref "SV301") (pin "2") (pinfunction "2_2") (pintype "passive"))
      (node (ref "Z303") (pin "5") (pinfunction "C4_5") (pintype "passive"))
      (node (ref "Z303") (pin "6") (pinfunction "D4_6") (pintype "passive"))
    )
    (net (code "46") (name "MAINBUS_SCK") (class "Default")
      (node (ref "IC101") (pin "65") (pinfunction "PE12_65") (pintype "bidirectional"))
      (node (ref "SV301") (pin "11") (pinfunction "11_11") (pintype "passive"))
      (node (ref "Z304") (pin "4") (pinfunction "C3_4") (pintype "passive"))
      (node (ref "Z304") (pin "7") (pinfunction "D3_7") (pintype "passive"))
    )
    (net (code "47") (name "MODULE_CE") (class "Default")
      (node (ref "IC101") (pin "22") (pinfunction "PF10_22") (pintype "bidirectional"))
    )
    (net (code "48") (name "MODULE_INT") (class "Default")
      (node (ref "IC101") (pin "18") (pinfunction "PF6_18") (pintype "bidirectional"))
      (node (ref "J302") (pin "10") (pinfunction "14_10") (pintype "passive"))
      (node (ref "Z307") (pin "1") (pinfunction "C1_1") (pintype "passive"))
      (node (ref "Z307") (pin "10") (pinfunction "D1_10") (pintype "passive"))
    )
    (net (code "49") (name "MODULE_MISO") (class "Default")
      (node (ref "IC101") (pin "20") (pinfunction "PF8_20") (pintype "bidirectional"))
      (node (ref "J302") (pin "14") (pinfunction "12_14") (pintype "passive"))
      (node (ref "R303") (pin "1") (pinfunction "1_1") (pintype "passive"))
      (node (ref "Z307") (pin "4") (pinfunction "C3_4") (pintype "passive"))
      (node (ref "Z307") (pin "7") (pinfunction "D3_7") (pintype "passive"))
    )
    (net (code "50") (name "MODULE_MOSI") (class "Default")
      (node (ref "IC101") (pin "21") (pinfunction "PF9_21") (pintype "bidirectional"))
      (node (ref "J302") (pin "12") (pinfunction "13_12") (pintype "passive"))
      (node (ref "Z307") (pin "5") (pinfunction "C4_5") (pintype "passive"))
      (node (ref "Z307") (pin "6") (pinfunction "D4_6") (pintype "passive"))
    )
    (net (code "51") (name "MODULE_NCS_BL") (class "Default")
      (node (ref "IC101") (pin "87") (pinfunction "PG2_87") (pintype "bidirectional"))
      (node (ref "J304") (pin "7") (pinfunction "4_7") (pintype "passive"))
      (node (ref "Z302") (pin "4") (pinfunction "C3_4") (pintype "passive"))
      (node (ref "Z302") (pin "7") (pinfunction "D3_7") (pintype "passive"))
    )
    (net (code "52") (name "MODULE_NCS_CC") (class "Default")
      (node (ref "IC101") (pin "90") (pinfunction "PG5_90") (pintype "bidirectional"))
      (node (ref "J304") (pin "1") (pinfunction "1_1") (pintype "passive"))
      (node (ref "Z301") (pin "1") (pinfunction "C1_1") (pintype "passive"))
      (node (ref "Z301") (pin "10") (pinfunction "D1_10") (pintype "passive"))
    )
    (net (code "53") (name "MODULE_NCS_CL") (class "Default")
      (node (ref "IC101") (pin "89") (pinfunction "PG4_89") (pintype "bidirectional"))
      (node (ref "J304") (pin "3") (pinfunction "2_3") (pintype "passive"))
      (node (ref "Z302") (pin "1") (pinfunction "C1_1") (pintype "passive"))
      (node (ref "Z302") (pin "10") (pinfunction "D1_10") (pintype "passive"))
    )
    (net (code "54") (name "MODULE_NCS_CR") (class "Default")
      (node (ref "IC101") (pin "92") (pinfunction "PG7_92") (pintype "bidirectional"))
      (node (ref "J304") (pin "8") (pinfunction "15_8") (pintype "passive"))
      (node (ref "Z301") (pin "4") (pinfunction "C3_4") (pintype "passive"))
      (node (ref "Z301") (pin "7") (pinfunction "D3_7") (pintype "passive"))
    )
    (net (code "55") (name "MODULE_NCS_FL") (class "Default")
      (node (ref "IC101") (pin "88") (pinfunction "PG3_88") (pintype "bidirectional"))
      (node (ref "J304") (pin "5") (pinfunction "3_5") (pintype "passive"))
      (node (ref "Z302") (pin "2") (pinfunction "C2_2") (pintype "passive"))
      (node (ref "Z302") (pin "9") (pinfunction "D2_9") (pintype "passive"))
    )
    (net (code "56") (name "MODULE_NCS_FR") (class "Default")
      (node (ref "IC101") (pin "93") (pinfunction "PG8_93") (pintype "bidirectional"))
      (node (ref "J304") (pin "6") (pinfunction "16_6") (pintype "passive"))
      (node (ref "Z301") (pin "5") (pinfunction "C4_5") (pintype "passive"))
      (node (ref "Z301") (pin "6") (pinfunction "D4_6") (pintype "passive"))
    )
    (net (code "57") (name "MODULE_NCS_TR") (class "Default")
      (node (ref "IC101") (pin "91") (pinfunction "PG6_91") (pintype "bidirectional"))
      (node (ref "J304") (pin "10") (pinfunction "14_10") (pintype "passive"))
      (node (ref "Z301") (pin "2") (pinfunction "C2_2") (pintype "passive"))
      (node (ref "Z301") (pin "9") (pinfunction "D2_9") (pintype "passive"))
    )
    (net (code "58") (name "MODULE_SCK") (class "Default")
      (node (ref "IC101") (pin "19") (pinfunction "PF7_19") (pintype "bidirectional"))
      (node (ref "J302") (pin "16") (pinfunction "11_16") (pintype "passive"))
      (node (ref "Z307") (pin "2") (pinfunction "C2_2") (pintype "passive"))
      (node (ref "Z307") (pin "9") (pinfunction "D2_9") (pintype "passive"))
    )
    (net (code "59") (name "NRST") (class "Default")
      (node (ref "IC101") (pin "25") (pinfunction "NRST_25") (pintype "input"))
      (node (ref "J302") (pin "18") (pinfunction "10_18") (pintype "passive"))
      (node (ref "U101") (pin "4") (pinfunction "O_4") (pintype "tri_state"))
    )
    (net (code "60") (name "NRST_") (class "Default")
      (node (ref "CON301") (pin "9") (pinfunction "9_9") (pintype "passive"))
      (node (ref "R101") (pin "1") (pinfunction "1_1") (pintype "passive"))
      (node (ref "U101") (pin "1") (pinfunction "OE_1") (pintype "input"))
      (node (ref "U101") (pin "2") (pinfunction "I_2") (pintype "input"))
    )
    (net (code "61") (name "Net-(CON301-Pad10)") (class "Default")
      (node (ref "CON301") (pin "10") (pinfunction "10_10") (pintype "passive"))
      (node (ref "R301") (pin "1") (pinfunction "1_1") (pintype "passive"))
    )
    (net (code "62") (name "Net-(D101-B)") (class "Default")
      (node (ref "D101") (pin "3") (pinfunction "B_3") (pintype "passive"))
      (node (ref "R106") (pin "2") (pinfunction "2_2") (pintype "passive"))
    )
    (net (code "63") (name "Net-(D101-G)") (class "Default")
      (node (ref "D101") (pin "2") (pinfunction "G_2") (pintype "passive"))
      (node (ref "R105") (pin "2") (pinfunction "2_2") (pintype "passive"))
    )
    (net (code "64") (name "Net-(D101-R)") (class "Default")
      (node (ref "D101") (pin "1") (pinfunction "R_1") (pintype "passive"))
      (node (ref "R104") (pin "2") (pinfunction "2_2") (pintype "passive"))
    )
    (net (code "65") (name "Net-(D102-PadC)") (class "Default")
      (node (ref "D102") (pin "C") (pinfunction "C_C") (pintype "passive"))
      (node (ref "R107") (pin "2") (pinfunction "2_2") (pintype "passive"))
    )
    (net (code "66") (name "Net-(D103-PadC)") (class "Default")
      (node (ref "D103") (pin "C") (pinfunction "C_C") (pintype "passive"))
      (node (ref "R108") (pin "2") (pinfunction "2_2") (pintype "passive"))
    )
    (net (code "67") (name "Net-(D104-PadC)") (class "Default")
      (node (ref "D104") (pin "C") (pinfunction "C_C") (pintype "passive"))
      (node (ref "R109") (pin "2") (pinfunction "2_2") (pintype "passive"))
    )
    (net (code "68") (name "Net-(D105-PadC)") (class "Default")
      (node (ref "D105") (pin "C") (pinfunction "C_C") (pintype "passive"))
      (node (ref "R111") (pin "2") (pinfunction "2_2") (pintype "passive"))
    )
    (net (code "69") (name "Net-(D106-PadC)") (class "Default")
      (node (ref "D106") (pin "C") (pinfunction "C_C") (pintype "passive"))
      (node (ref "R112") (pin "2") (pinfunction "2_2") (pintype "passive"))
    )
    (net (code "70") (name "Net-(D301-VDD)") (class "Default")
      (node (ref "D301") (pin "5") (pinfunction "VDD_5") (pintype "power_in"))
      (node (ref "J301") (pin "1") (pinfunction "1_1") (pintype "passive"))
      (node (ref "L301") (pin "2") (pinfunction "2_2") (pintype "passive"))
    )
    (net (code "71") (name "Net-(IC201A-+IN)") (class "Default")
      (node (ref "IC201") (pin "3") (pinfunction "+IN_3") (pintype "input"))
      (node (ref "R201") (pin "1") (pinfunction "1_1") (pintype "passive"))
      (node (ref "R203") (pin "2") (pinfunction "2_2") (pintype "passive"))
    )
    (net (code "72") (name "Net-(IC201A--IN)") (class "Default")
      (node (ref "C201") (pin "2") (pinfunction "2_2") (pintype "passive"))
      (node (ref "IC201") (pin "2") (pinfunction "-IN_2") (pintype "input"))
      (node (ref "R205") (pin "1") (pinfunction "1_1") (pintype "passive"))
      (node (ref "R207") (pin "2") (pinfunction "2_2") (pintype "passive"))
    )
    (net (code "73") (name "Net-(IC201B-+IN)") (class "Default")
      (node (ref "IC201") (pin "5") (pinfunction "+IN_5") (pintype "input"))
      (node (ref "R202") (pin "1") (pinfunction "1_1") (pintype "passive"))
      (node (ref "R204") (pin "2") (pinfunction "2_2") (pintype "passive"))
    )
    (net (code "74") (name "Net-(IC201B--IN)") (class "Default")
      (node (ref "C202") (pin "2") (pinfunction "2_2") (pintype "passive"))
      (node (ref "IC201") (pin "6") (pinfunction "-IN_6") (pintype "input"))
      (node (ref "R206") (pin "1") (pinfunction "1_1") (pintype "passive"))
      (node (ref "R208") (pin "2") (pinfunction "2_2") (pintype "passive"))
    )
    (net (code "75") (name "Net-(J301-Pad4)") (class "Default")
      (node (ref "J301") (pin "4") (pinfunction "4_4") (pintype "passive"))
      (node (ref "R304") (pin "2") (pinfunction "2_2") (pintype "passive"))
    )
    (net (code "76") (name "Net-(J303-PadB)") (class "Default")
      (node (ref "J303") (pin "B") (pinfunction "B_B") (pintype "bidirectional"))
      (node (ref "R307") (pin "1") (pinfunction "1_1") (pintype "passive"))
    )
    (net (code "77") (name "Net-(J305-Pad5)") (class "Default")
      (node (ref "J305") (pin "5") (pinfunction "5_5") (pintype "passive"))
      (node (ref "R306") (pin "1") (pinfunction "1_1") (pintype "passive"))
    )
    (net (code "78") (name "Net-(L302-1)") (class "Default")
      (node (ref "D301") (pin "1") (pinfunction "1_1") (pintype "bidirectional"))
      (node (ref "J301") (pin "3") (pinfunction "3_3") (pintype "passive"))
      (node (ref "L302") (pin "4") (pinfunction "1_4") (pintype "passive"))
    )
    (net (code "79") (name "Net-(L302-4)") (class "Default")
      (node (ref "D301") (pin "6") (pinfunction "6_6") (pintype "bidirectional"))
      (node (ref "J301") (pin "2") (pinfunction "2_2") (pintype "passive"))
      (node (ref "L302") (pin "1") (pinfunction "4_1") (pintype "passive"))
    )
    (net (code "80") (name "Net-(U201-FSYNC)") (class "Default")
      (node (ref "R209") (pin "1") (pinfunction "1_1") (pintype "passive"))
      (node (ref "R210") (pin "2") (pinfunction "2_2") (pintype "passive"))
      (node (ref "U201") (pin "P8") (pinfunction "FSYNC_P8") (pintype "bidirectional"))
    )
    (net (code "81") (name "Net-(U201-REGOUT)") (class "Default")
      (node (ref "C210") (pin "1") (pinfunction "1_1") (pintype "passive"))
      (node (ref "U201") (pin "P14") (pinfunction "REGOUT_P14") (pintype "bidirectional"))
    )
    (net (code "82") (name "OSC_IN") (class "Default")
      (node (ref "IC101") (pin "23") (pinfunction "PH0_23") (pintype "bidirectional"))
      (node (ref "Y101") (pin "P3") (pinfunction "OUT_P3") (pintype "output"))
    )
    (net (code "83") (name "OSC_OUT") (class "Default")
      (node (ref "IC101") (pin "24") (pinfunction "PH1_24") (pintype "bidirectional"))
    )
    (net (code "84") (name "SD_CLK") (class "Default")
      (node (ref "IC101") (pin "113") (pinfunction "PC12_113") (pintype "bidirectional"))
      (node (ref "J303") (pin "5") (pinfunction "CLK_5") (pintype "bidirectional"))
    )
    (net (code "85") (name "SD_CMD") (class "Default")
      (node (ref "IC101") (pin "116") (pinfunction "PD2_116") (pintype "bidirectional"))
      (node (ref "J303") (pin "3") (pinfunction "CMD/MOSI_3") (pintype "bidirectional"))
    )
    (net (code "86") (name "SD_DATA0") (class "Default")
      (node (ref "IC101") (pin "98") (pinfunction "PC8_98") (pintype "bidirectional"))
      (node (ref "J303") (pin "7") (pinfunction "DATA0/MISO_7") (pintype "bidirectional"))
    )
    (net (code "87") (name "SD_DATA1") (class "Default")
      (node (ref "IC101") (pin "99") (pinfunction "PC9_99") (pintype "bidirectional"))
      (node (ref "J303") (pin "8") (pinfunction "DATA1/RSV_8") (pintype "bidirectional"))
    )
    (net (code "88") (name "SD_DATA2") (class "Default")
      (node (ref "IC101") (pin "111") (pinfunction "PC10_111") (pintype "bidirectional"))
      (node (ref "J303") (pin "1") (pinfunction "DATA2/NC_1") (pintype "bidirectional"))
    )
    (net (code "89") (name "SD_DATA3") (class "Default")
      (node (ref "IC101") (pin "112") (pinfunction "PC11_112") (pintype "bidirectional"))
      (node (ref "J303") (pin "2") (pinfunction "DATA3-CD/CS_N_2") (pintype "bidirectional"))
    )
    (net (code "90") (name "SD_DETECT") (class "Default")
      (node (ref "C302") (pin "1") (pinfunction "1_1") (pintype "passive"))
      (node (ref "IC101") (pin "114") (pinfunction "PD0_114") (pintype "bidirectional"))
      (node (ref "R307") (pin "2") (pinfunction "2_2") (pintype "passive"))
    )
    (net (code "91") (name "SD_EJECT") (class "Default")
      (node (ref "IC101") (pin "122") (pinfunction "PD6_122") (pintype "bidirectional"))
      (node (ref "R306") (pin "2") (pinfunction "2_2") (pintype "passive"))
    )
    (net (code "92") (name "USART3_CTS") (class "Default")
      (node (ref "IC101") (pin "74") (pinfunction "PB13_74") (pintype "bidirectional"))
      (node (ref "J304") (pin "11") (pinfunction "6_11") (pintype "passive"))
      (node (ref "Z303") (pin "1") (pinfunction "C1_1") (pintype "passive"))
      (node (ref "Z303") (pin "10") (pinfunction "D1_10") (pintype "passive"))
    )
    (net (code "93") (name "USART3_RTS") (class "Default")
      (node (ref "IC101") (pin "75") (pinfunction "PB14_75") (pintype "bidirectional"))
      (node (ref "J304") (pin "4") (pinfunction "17_4") (pintype "passive"))
      (node (ref "Z302") (pin "5") (pinfunction "C4_5") (pintype "passive"))
      (node (ref "Z302") (pin "6") (pinfunction "D4_6") (pintype "passive"))
    )
    (net (code "94") (name "USART3_RX") (class "Default")
      (node (ref "IC101") (pin "70") (pinfunction "PB11_70") (pintype "bidirectional"))
      (node (ref "J304") (pin "12") (pinfunction "13_12") (pintype "passive"))
      (node (ref "Z303") (pin "2") (pinfunction "C2_2") (pintype "passive"))
      (node (ref "Z303") (pin "9") (pinfunction "D2_9") (pintype "passive"))
    )
    (net (code "95") (name "USART3_TX") (class "Default")
      (node (ref "IC101") (pin "69") (pinfunction "PB10_69") (pintype "bidirectional"))
      (node (ref "J304") (pin "9") (pinfunction "5_9") (pintype "passive"))
      (node (ref "Z303") (pin "4") (pinfunction "C3_4") (pintype "passive"))
      (node (ref "Z303") (pin "7") (pinfunction "D3_7") (pintype "passive"))
    )
    (net (code "96") (name "USBOTG_DM") (class "Default")
      (node (ref "IC101") (pin "103") (pinfunction "PA11_103") (pintype "bidirectional"))
      (node (ref "L302") (pin "2") (pinfunction "3_2") (pintype "passive"))
    )
    (net (code "97") (name "USBOTG_DP") (class "Default")
      (node (ref "IC101") (pin "104") (pinfunction "PA12_104") (pintype "bidirectional"))
      (node (ref "L302") (pin "3") (pinfunction "2_3") (pintype "passive"))
    )
    (net (code "98") (name "USBOTG_EN_PWR") (class "Default")
      (node (ref "IC101") (pin "101") (pinfunction "PA9_101") (pintype "bidirectional"))
      (node (ref "IC202") (pin "4") (pinfunction "ENABLE_4") (pintype "input"))
    )
    (net (code "99") (name "USBOTG_ID") (class "Default")
      (node (ref "IC101") (pin "102") (pinfunction "PA10_102") (pintype "bidirectional"))
    )
    (net (code "100") (name "USBOTG_OVRCRT") (class "Default")
      (node (ref "IC101") (pin "100") (pinfunction "PA8_100") (pintype "bidirectional"))
      (node (ref "IC202") (pin "3") (pinfunction "FAULT_3") (pintype "open_collector"))
    )
    (net (code "101") (name "USBOTG_VBUS") (class "Default")
      (node (ref "C212") (pin "1") (pinfunction "1_1") (pintype "passive"))
      (node (ref "IC202") (pin "1") (pinfunction "OUT_1") (pintype "power_in"))
      (node (ref "L301") (pin "1") (pinfunction "1_1") (pintype "passive"))
    )
    (net (code "102") (name "U_BAT_1") (class "Default")
      (node (ref "C201") (pin "1") (pinfunction "1_1") (pintype "passive"))
      (node (ref "D202") (pin "C") (pinfunction "KATHODE_C") (pintype "bidirectional"))
      (node (ref "IC101") (pin "47") (pinfunction "PB1_47") (pintype "bidirectional"))
      (node (ref "IC201") (pin "1") (pinfunction "OUT_1") (pintype "output"))
      (node (ref "R205") (pin "2") (pinfunction "2_2") (pintype "passive"))
    )
    (net (code "103") (name "U_BAT_2") (class "Default")
      (node (ref "C202") (pin "1") (pinfunction "1_1") (pintype "passive"))
      (node (ref "D201") (pin "C") (pinfunction "KATHODE_C") (pintype "bidirectional"))
      (node (ref "IC101") (pin "46") (pinfunction "PB0_46") (pintype "bidirectional"))
      (node (ref "IC201") (pin "7") (pinfunction "OUT_7") (pintype "output"))
      (node (ref "R206") (pin "2") (pinfunction "2_2") (pintype "passive"))
    )
    (net (code "104") (name "VCAP_1") (class "Default")
      (node (ref "C113") (pin "1") (pinfunction "1_1") (pintype "passive"))
      (node (ref "IC101") (pin "71") (pinfunction "VCAP_1_71") (pintype "bidirectional"))
    )
    (net (code "105") (name "VCAP_2") (class "Default")
      (node (ref "C112") (pin "1") (pinfunction "1_1") (pintype "passive"))
      (node (ref "IC101") (pin "106") (pinfunction "VCAP_2_106") (pintype "bidirectional"))
    )
    (net (code "106") (name "VCC") (class "Default")
      (node (ref "J302") (pin "4") (pinfunction "17_4") (pintype "passive"))
      (node (ref "J304") (pin "15") (pinfunction "8_15") (pintype "passive"))
      (node (ref "SV301") (pin "8") (pinfunction "8_8") (pintype "passive"))
    )
    (net (code "107") (name "VDDA") (class "Default")
      (node (ref "C104") (pin "1") (pinfunction "1_1") (pintype "passive"))
      (node (ref "C105") (pin "1") (pinfunction "1_1") (pintype "passive"))
      (node (ref "IC101") (pin "33") (pinfunction "VDDA_33") (pintype "power_in"))
      (node (ref "R103") (pin "2") (pinfunction "2_2") (pintype "passive"))
    )
    (net (code "108") (name "VDD_") (class "Default")
      (node (ref "R201") (pin "2") (pinfunction "2_2") (pintype "passive"))
      (node (ref "SV301") (pin "10") (pinfunction "10_10") (pintype "passive"))
    )
    (net (code "109") (name "VREF+") (class "Default")
      (node (ref "C103") (pin "1") (pinfunction "1_1") (pintype "passive"))
      (node (ref "IC101") (pin "32") (pinfunction "VREF+_32") (pintype "input"))
      (node (ref "R102") (pin "2") (pinfunction "2_2") (pintype "passive"))
    )
    (net (code "110") (name "unconnected-(D301-Pad3)") (class "Default")
      (node (ref "D301") (pin "3") (pinfunction "3_3") (pintype "bidirectional"))
    )
    (net (code "111") (name "unconnected-(D301-Pad4)") (class "Default")
      (node (ref "D301") (pin "4") (pinfunction "4_4") (pintype "bidirectional"))
    )
    (net (code "112") (name "unconnected-(IC101-PA1-Pad35)") (class "Default")
      (node (ref "IC101") (pin "35") (pinfunction "PA1_35") (pintype "bidirectional"))
    )
    (net (code "113") (name "unconnected-(IC101-PA2-Pad36)") (class "Default")
      (node (ref "IC101") (pin "36") (pinfunction "PA2_36") (pintype "bidirectional"))
    )
    (net (code "114") (name "unconnected-(IC101-PA3-Pad37)") (class "Default")
      (node (ref "IC101") (pin "37") (pinfunction "PA3_37") (pintype "bidirectional"))
    )
    (net (code "115") (name "unconnected-(IC101-PB2-Pad48)") (class "Default")
      (node (ref "IC101") (pin "48") (pinfunction "PB2_48") (pintype "bidirectional"))
    )
    (net (code "116") (name "unconnected-(IC101-PB5-Pad135)") (class "Default")
      (node (ref "IC101") (pin "135") (pinfunction "PB5_135") (pintype "bidirectional"))
    )
    (net (code "117") (name "unconnected-(IC101-PB7-Pad137)") (class "Default")
      (node (ref "IC101") (pin "137") (pinfunction "PB7_137") (pintype "bidirectional"))
    )
    (net (code "118") (name "unconnected-(IC101-PB12-Pad73)") (class "Default")
      (node (ref "IC101") (pin "73") (pinfunction "PB12_73") (pintype "bidirectional"))
    )
    (net (code "119") (name "unconnected-(IC101-PB15-Pad76)") (class "Default")
      (node (ref "IC101") (pin "76") (pinfunction "PB15_76") (pintype "bidirectional"))
    )
    (net (code "120") (name "unconnected-(IC101-PC0-Pad26)") (class "Default")
      (node (ref "IC101") (pin "26") (pinfunction "PC0_26") (pintype "bidirectional"))
    )
    (net (code "121") (name "unconnected-(IC101-PC1-Pad27)") (class "Default")
      (node (ref "IC101") (pin "27") (pinfunction "PC1_27") (pintype "bidirectional"))
    )
    (net (code "122") (name "unconnected-(IC101-PC2-Pad28)") (class "Default")
      (node (ref "IC101") (pin "28") (pinfunction "PC2_28") (pintype "bidirectional"))
    )
    (net (code "123") (name "unconnected-(IC101-PC3-Pad29)") (class "Default")
      (node (ref "IC101") (pin "29") (pinfunction "PC3_29") (pintype "bidirectional"))
    )
    (net (code "124") (name "unconnected-(IC101-PC5-Pad45)") (class "Default")
      (node (ref "IC101") (pin "45") (pinfunction "PC5_45") (pintype "bidirectional"))
    )
    (net (code "125") (name "unconnected-(IC101-PC6-Pad96)") (class "Default")
      (node (ref "IC101") (pin "96") (pinfunction "PC6_96") (pintype "bidirectional"))
    )
    (net (code "126") (name "unconnected-(IC101-PC7-Pad97)") (class "Default")
      (node (ref "IC101") (pin "97") (pinfunction "PC7_97") (pintype "bidirectional"))
    )
    (net (code "127") (name "unconnected-(IC101-PD1-Pad115)") (class "Default")
      (node (ref "IC101") (pin "115") (pinfunction "PD1_115") (pintype "bidirectional"))
    )
    (net (code "128") (name "unconnected-(IC101-PD3-Pad117)") (class "Default")
      (node (ref "IC101") (pin "117") (pinfunction "PD3_117") (pintype "bidirectional"))
    )
    (net (code "129") (name "unconnected-(IC101-PD4-Pad118)") (class "Default")
      (node (ref "IC101") (pin "118") (pinfunction "PD4_118") (pintype "bidirectional"))
    )
    (net (code "130") (name "unconnected-(IC101-PD5-Pad119)") (class "Default")
      (node (ref "IC101") (pin "119") (pinfunction "PD5_119") (pintype "bidirectional"))
    )
    (net (code "131") (name "unconnected-(IC101-PD7-Pad123)") (class "Default")
      (node (ref "IC101") (pin "123") (pinfunction "PD7_123") (pintype "bidirectional"))
    )
    (net (code "132") (name "unconnected-(IC101-PD9-Pad78)") (class "Default")
      (node (ref "IC101") (pin "78") (pinfunction "PD9_78") (pintype "bidirectional"))
    )
    (net (code "133") (name "unconnected-(IC101-PD10-Pad79)") (class "Default")
      (node (ref "IC101") (pin "79") (pinfunction "PD10_79") (pintype "bidirectional"))
    )
    (net (code "134") (name "unconnected-(IC101-PD11-Pad80)") (class "Default")
      (node (ref "IC101") (pin "80") (pinfunction "PD11_80") (pintype "bidirectional"))
    )
    (net (code "135") (name "unconnected-(IC101-PD12-Pad81)") (class "Default")
      (node (ref "IC101") (pin "81") (pinfunction "PD12_81") (pintype "bidirectional"))
    )
    (net (code "136") (name "unconnected-(IC101-PD13-Pad82)") (class "Default")
      (node (ref "IC101") (pin "82") (pinfunction "PD13_82") (pintype "bidirectional"))
    )
    (net (code "137") (name "unconnected-(IC101-PD14-Pad85)") (class "Default")
      (node (ref "IC101") (pin "85") (pinfunction "PD14_85") (pintype "bidirectional"))
    )
    (net (code "138") (name "unconnected-(IC101-PD15-Pad86)") (class "Default")
      (node (ref "IC101") (pin "86") (pinfunction "PD15_86") (pintype "bidirectional"))
    )
    (net (code "139") (name "unconnected-(IC101-PE3-Pad2)") (class "Default")
      (node (ref "IC101") (pin "2") (pinfunction "PE3_2") (pintype "bidirectional"))
    )
    (net (code "140") (name "unconnected-(IC101-PE4-Pad3)") (class "Default")
      (node (ref "IC101") (pin "3") (pinfunction "PE4_3") (pintype "bidirectional"))
    )
    (net (code "141") (name "unconnected-(IC101-PE5-Pad4)") (class "Default")
      (node (ref "IC101") (pin "4") (pinfunction "PE5_4") (pintype "bidirectional"))
    )
    (net (code "142") (name "unconnected-(IC101-PE6-Pad5)") (class "Default")
      (node (ref "IC101") (pin "5") (pinfunction "PE6_5") (pintype "bidirectional"))
    )
    (net (code "143") (name "unconnected-(IC101-PE8-Pad59)") (class "Default")
      (node (ref "IC101") (pin "59") (pinfunction "PE8_59") (pintype "bidirectional"))
    )
    (net (code "144") (name "unconnected-(IC101-PF2-Pad12)") (class "Default")
      (node (ref "IC101") (pin "12") (pinfunction "PF2_12") (pintype "bidirectional"))
    )
    (net (code "145") (name "unconnected-(IC101-PF11-Pad49)") (class "Default")
      (node (ref "IC101") (pin "49") (pinfunction "PF11_49") (pintype "bidirectional"))
    )
    (net (code "146") (name "unconnected-(IC101-PF12-Pad50)") (class "Default")
      (node (ref "IC101") (pin "50") (pinfunction "PF12_50") (pintype "bidirectional"))
    )
    (net (code "147") (name "unconnected-(IC101-PF13-Pad53)") (class "Default")
      (node (ref "IC101") (pin "53") (pinfunction "PF13_53") (pintype "bidirectional"))
    )
    (net (code "148") (name "unconnected-(IC101-PF14-Pad54)") (class "Default")
      (node (ref "IC101") (pin "54") (pinfunction "PF14_54") (pintype "bidirectional"))
    )
    (net (code "149") (name "unconnected-(IC101-PF15-Pad55)") (class "Default")
      (node (ref "IC101") (pin "55") (pinfunction "PF15_55") (pintype "bidirectional"))
    )
    (net (code "150") (name "unconnected-(IC101-PG0-Pad56)") (class "Default")
      (node (ref "IC101") (pin "56") (pinfunction "PG0_56") (pintype "bidirectional"))
    )
    (net (code "151") (name "unconnected-(IC101-PG9-Pad124)") (class "Default")
      (node (ref "IC101") (pin "124") (pinfunction "PG9_124") (pintype "bidirectional"))
    )
    (net (code "152") (name "unconnected-(IC101-PG15-Pad132)") (class "Default")
      (node (ref "IC101") (pin "132") (pinfunction "PG15_132") (pintype "bidirectional"))
    )
  )
)
